# PCB_-_BOARD.net
KiCad netlist of a schematic drawn in EAGLE
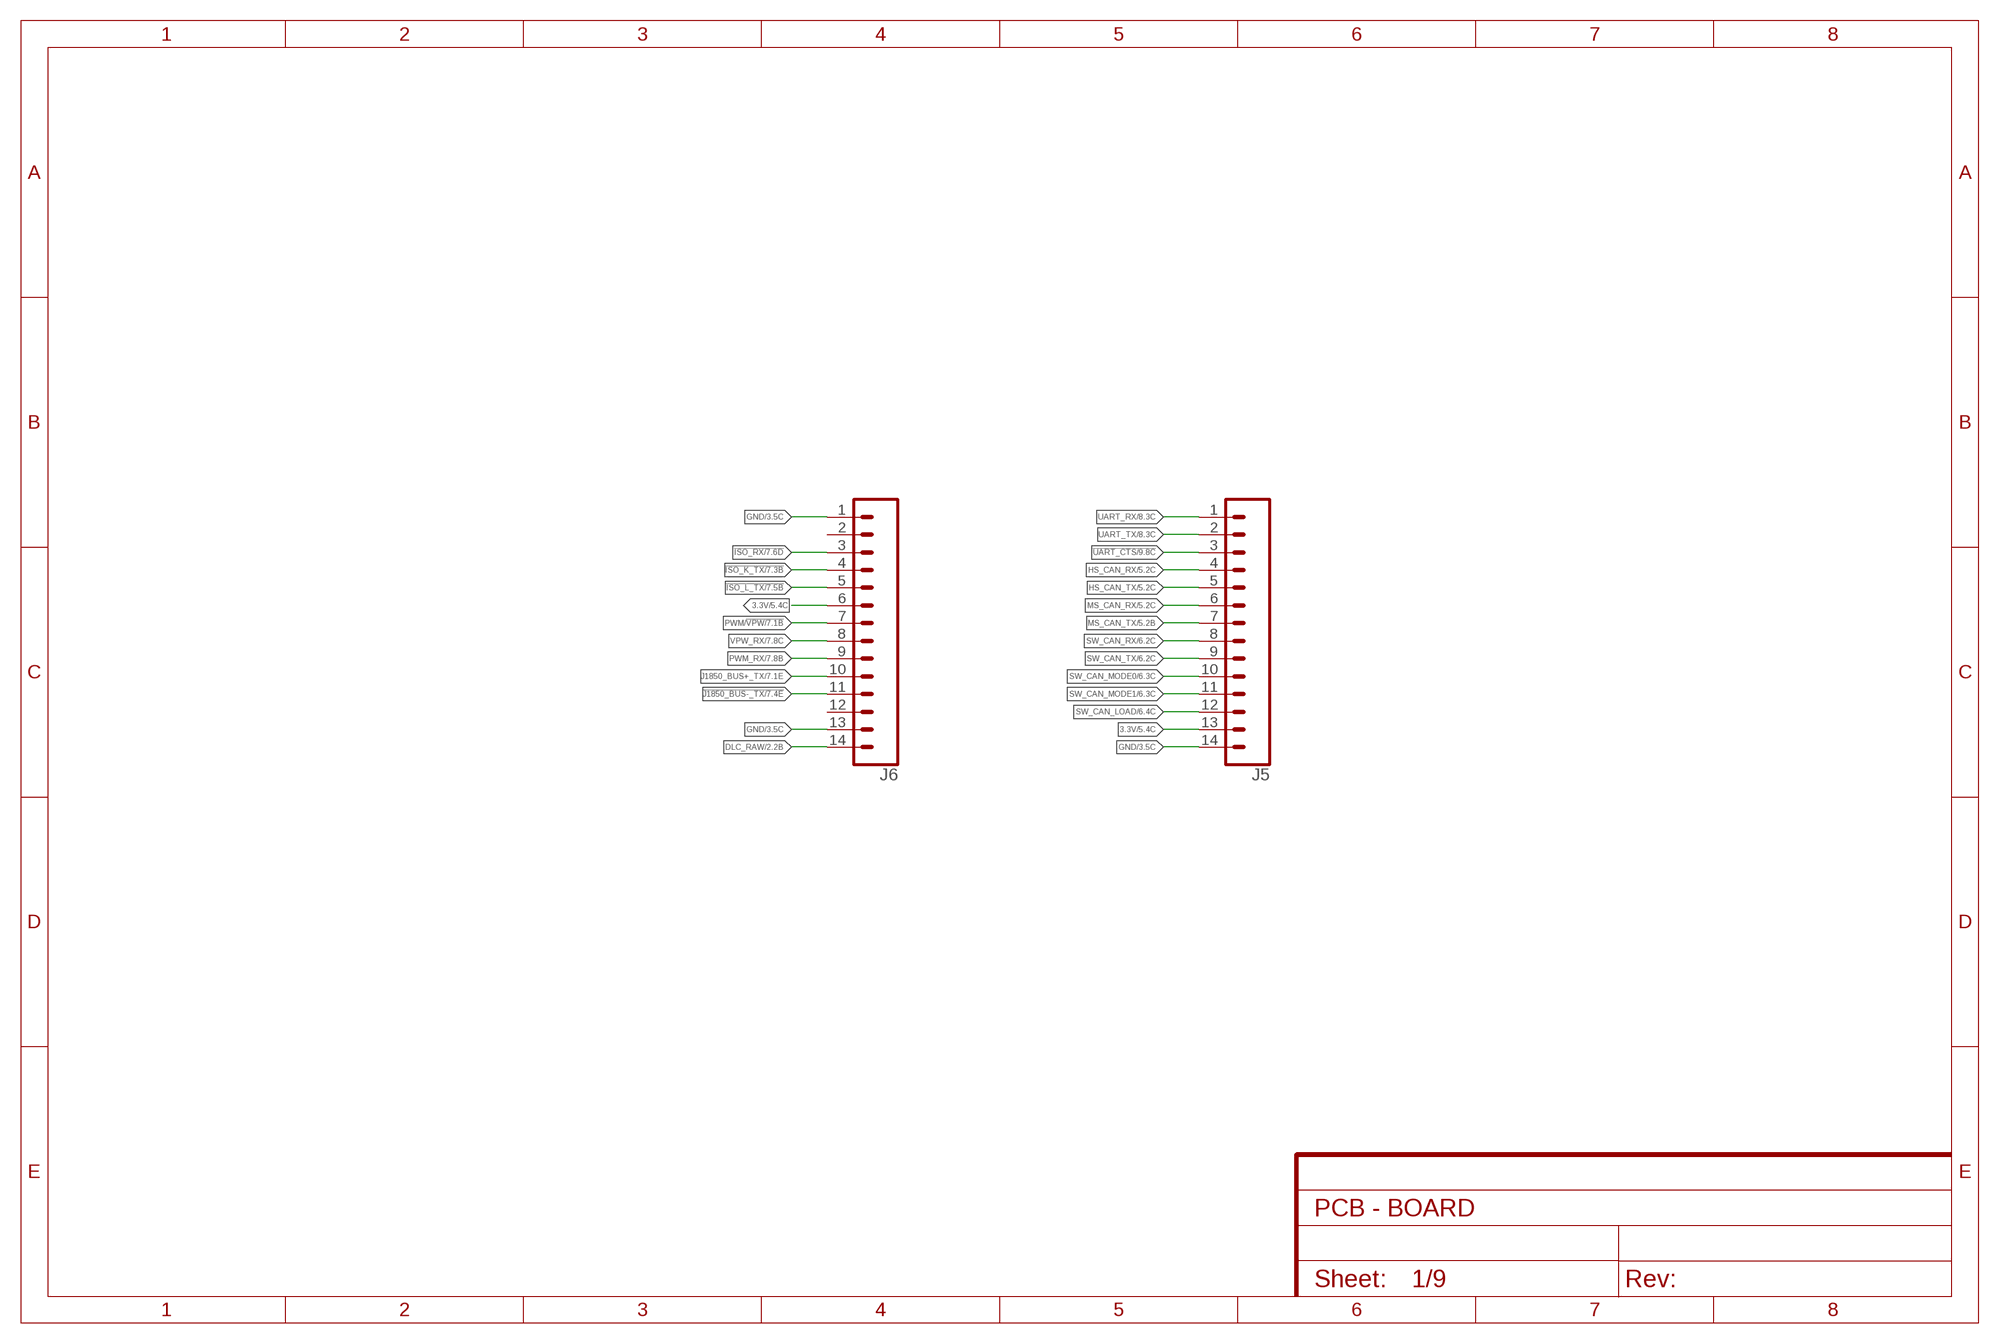
[diagram p0: schematic, sheet 1]
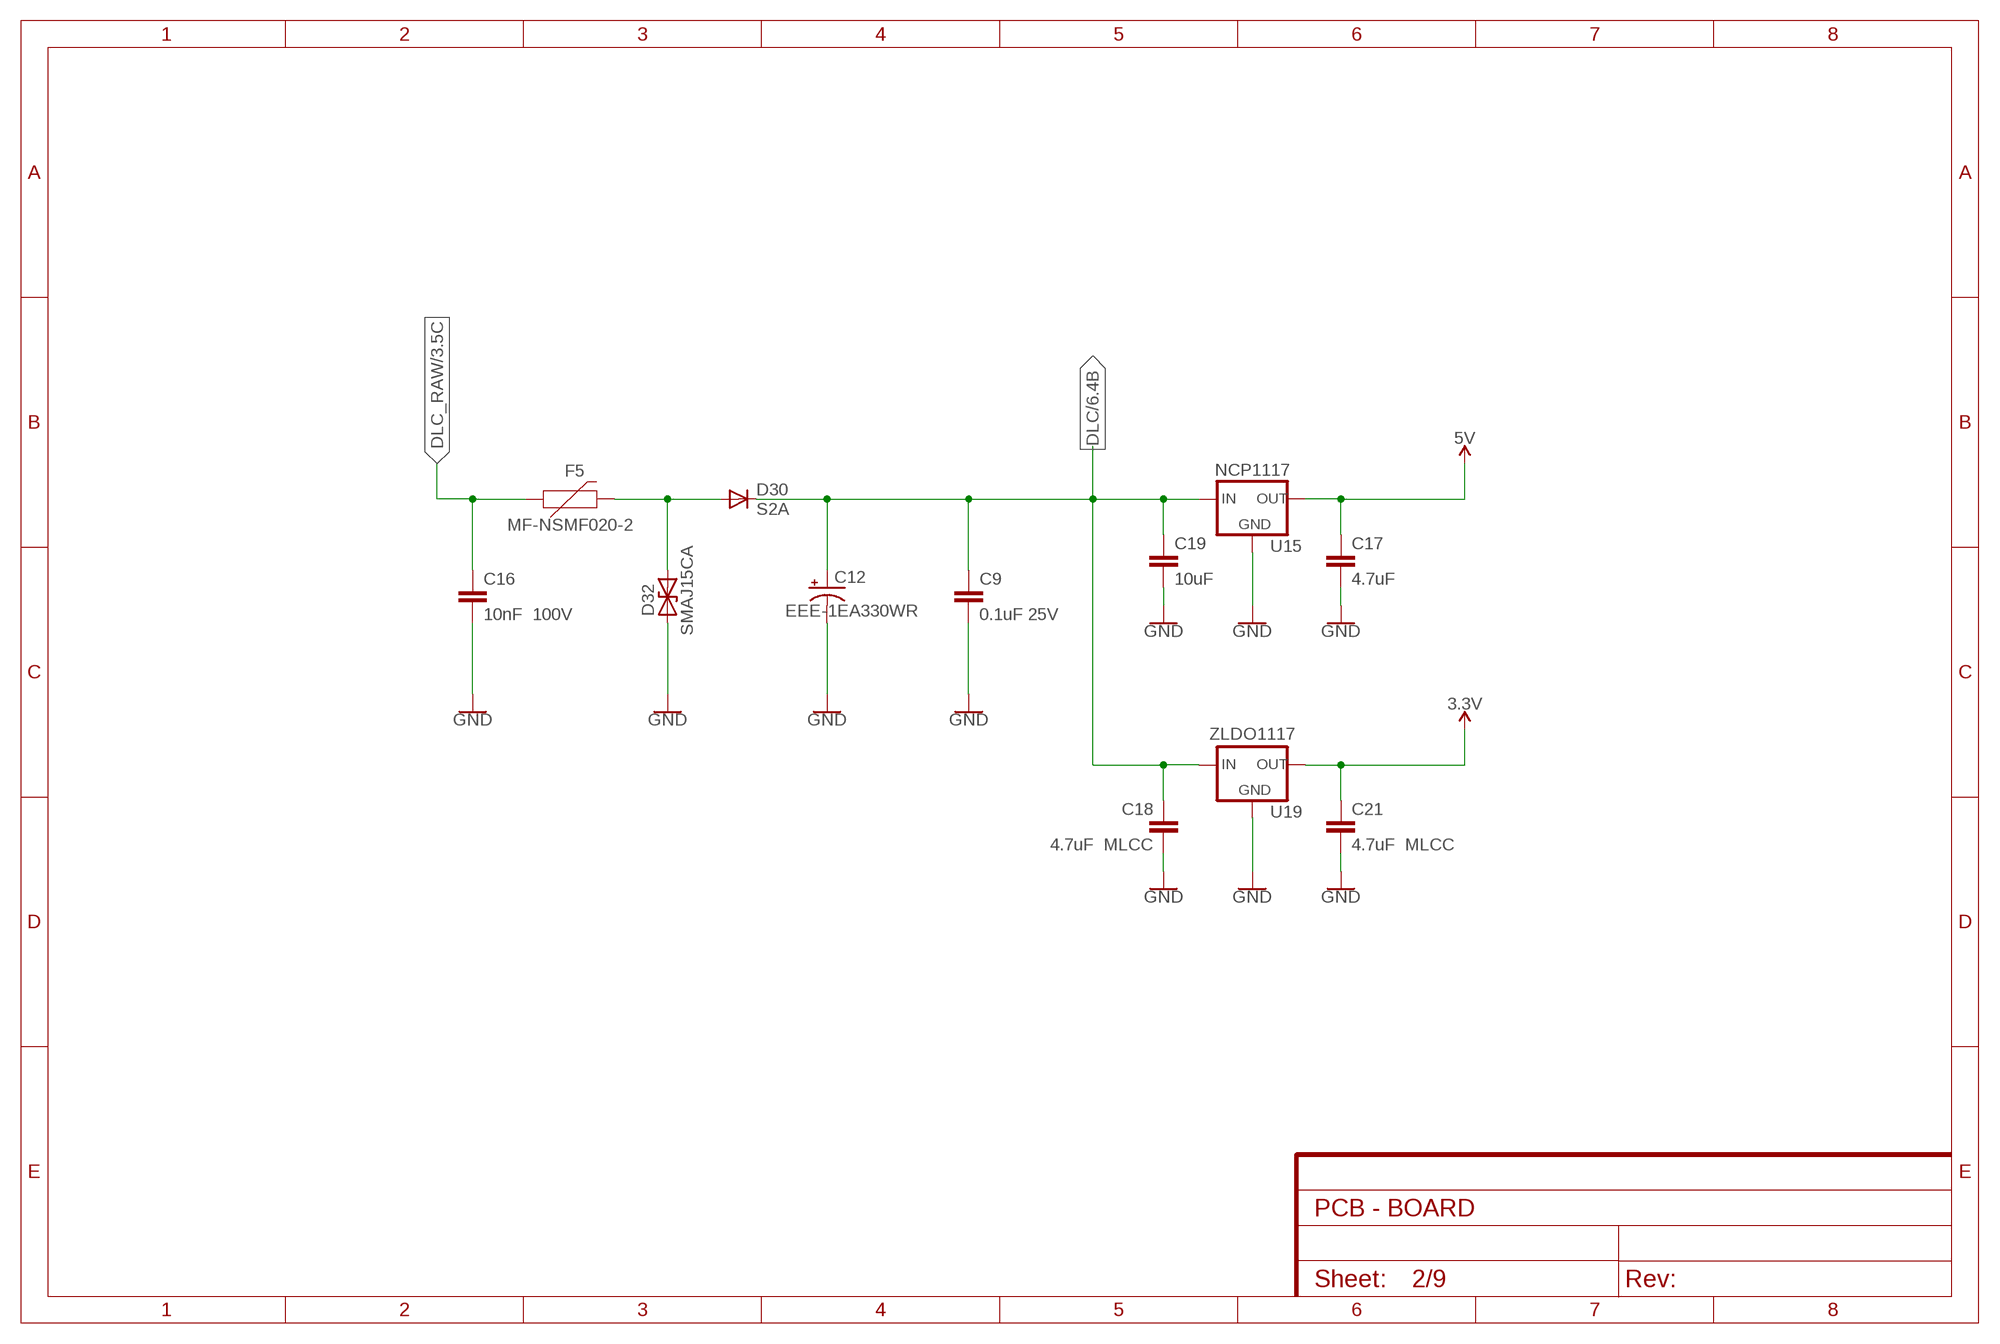
[diagram p1: schematic, sheet 2]
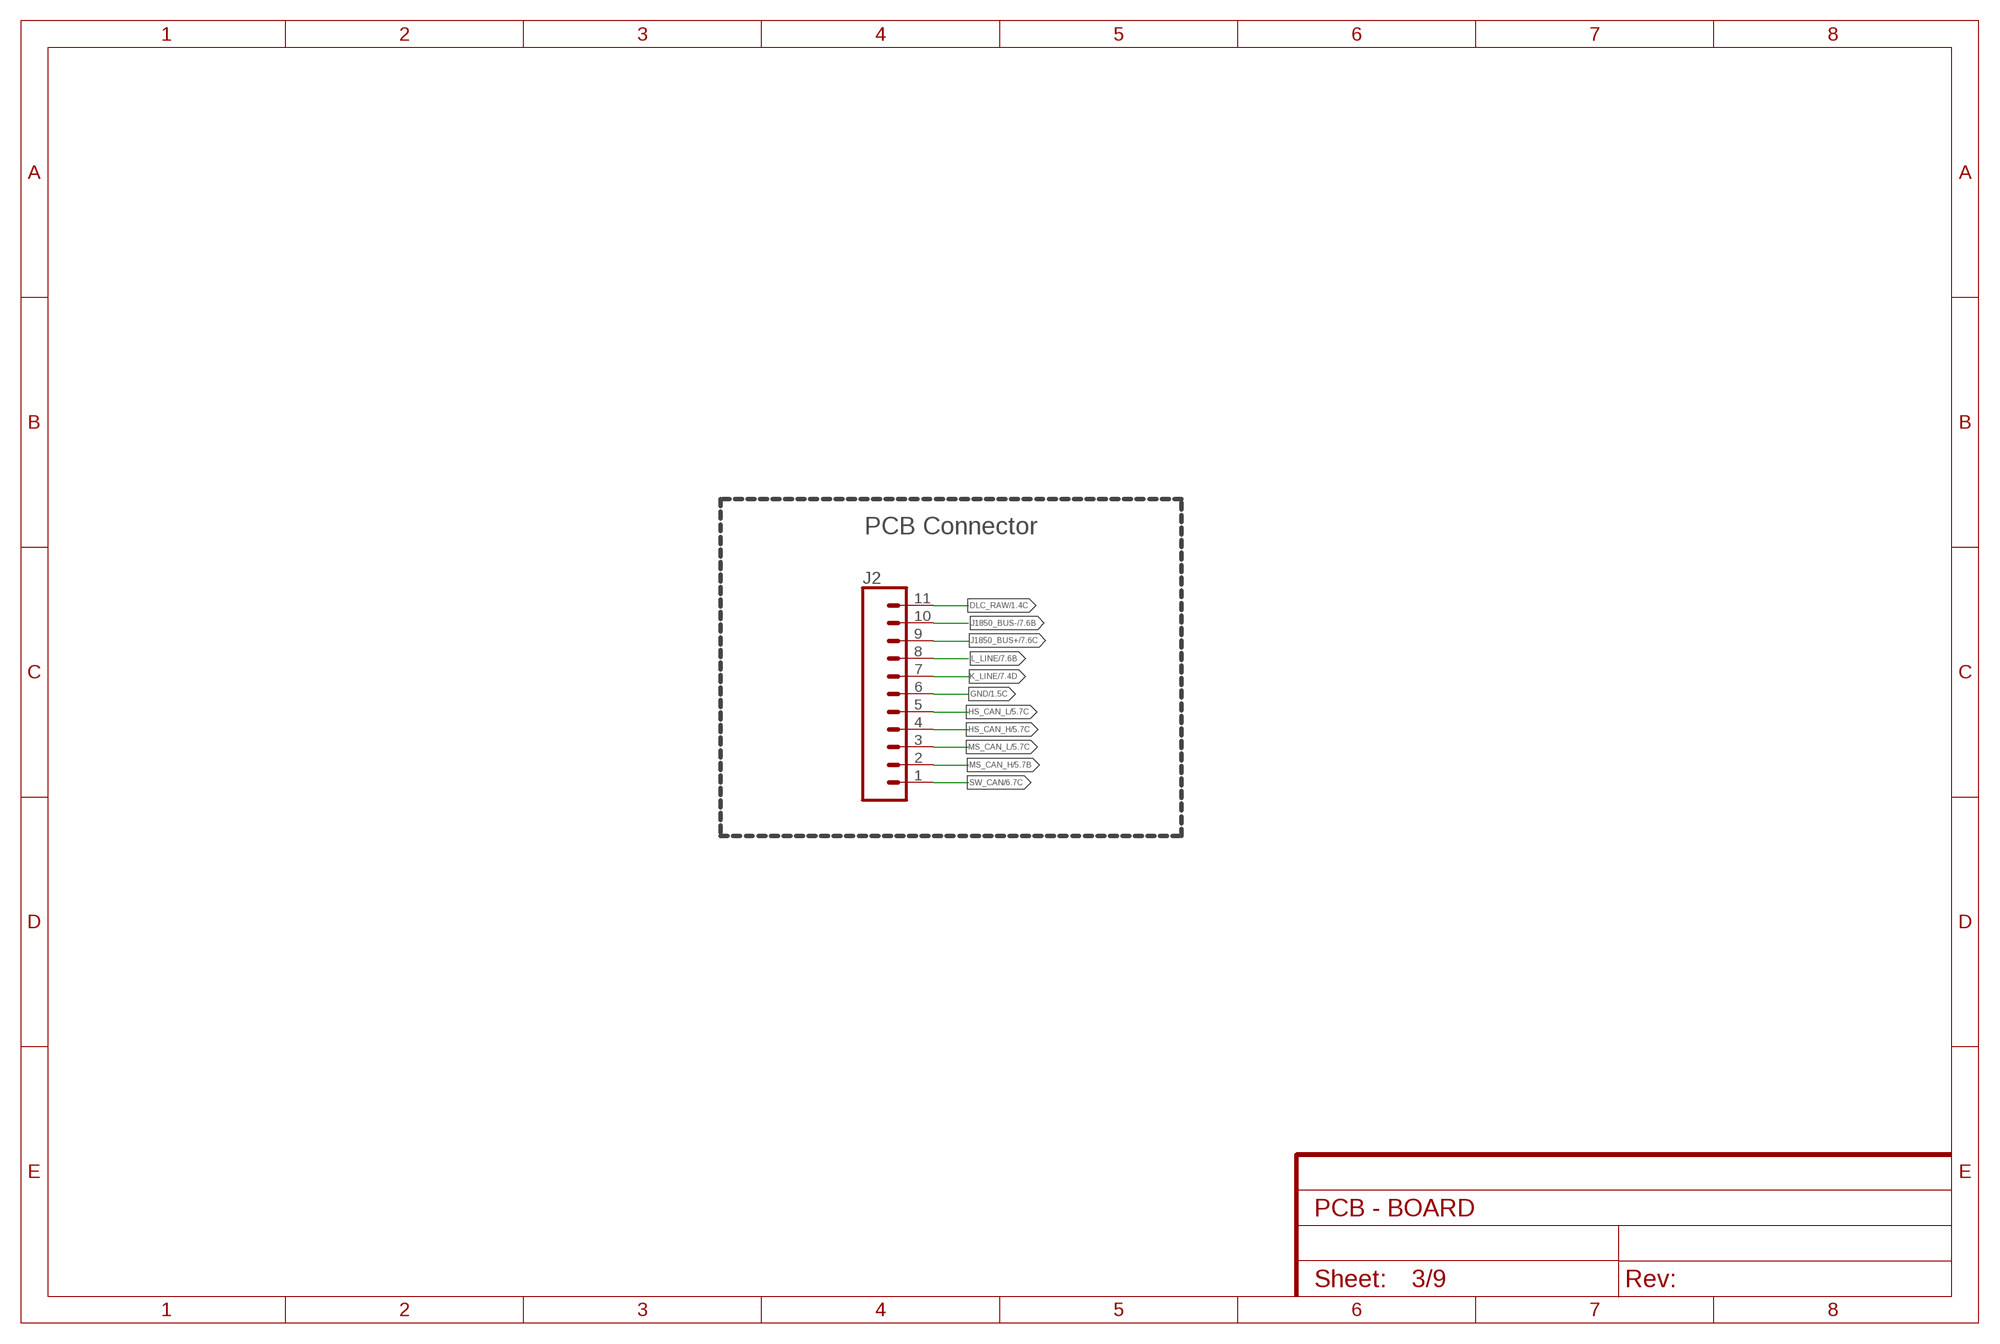
[diagram p2: schematic, sheet 3]
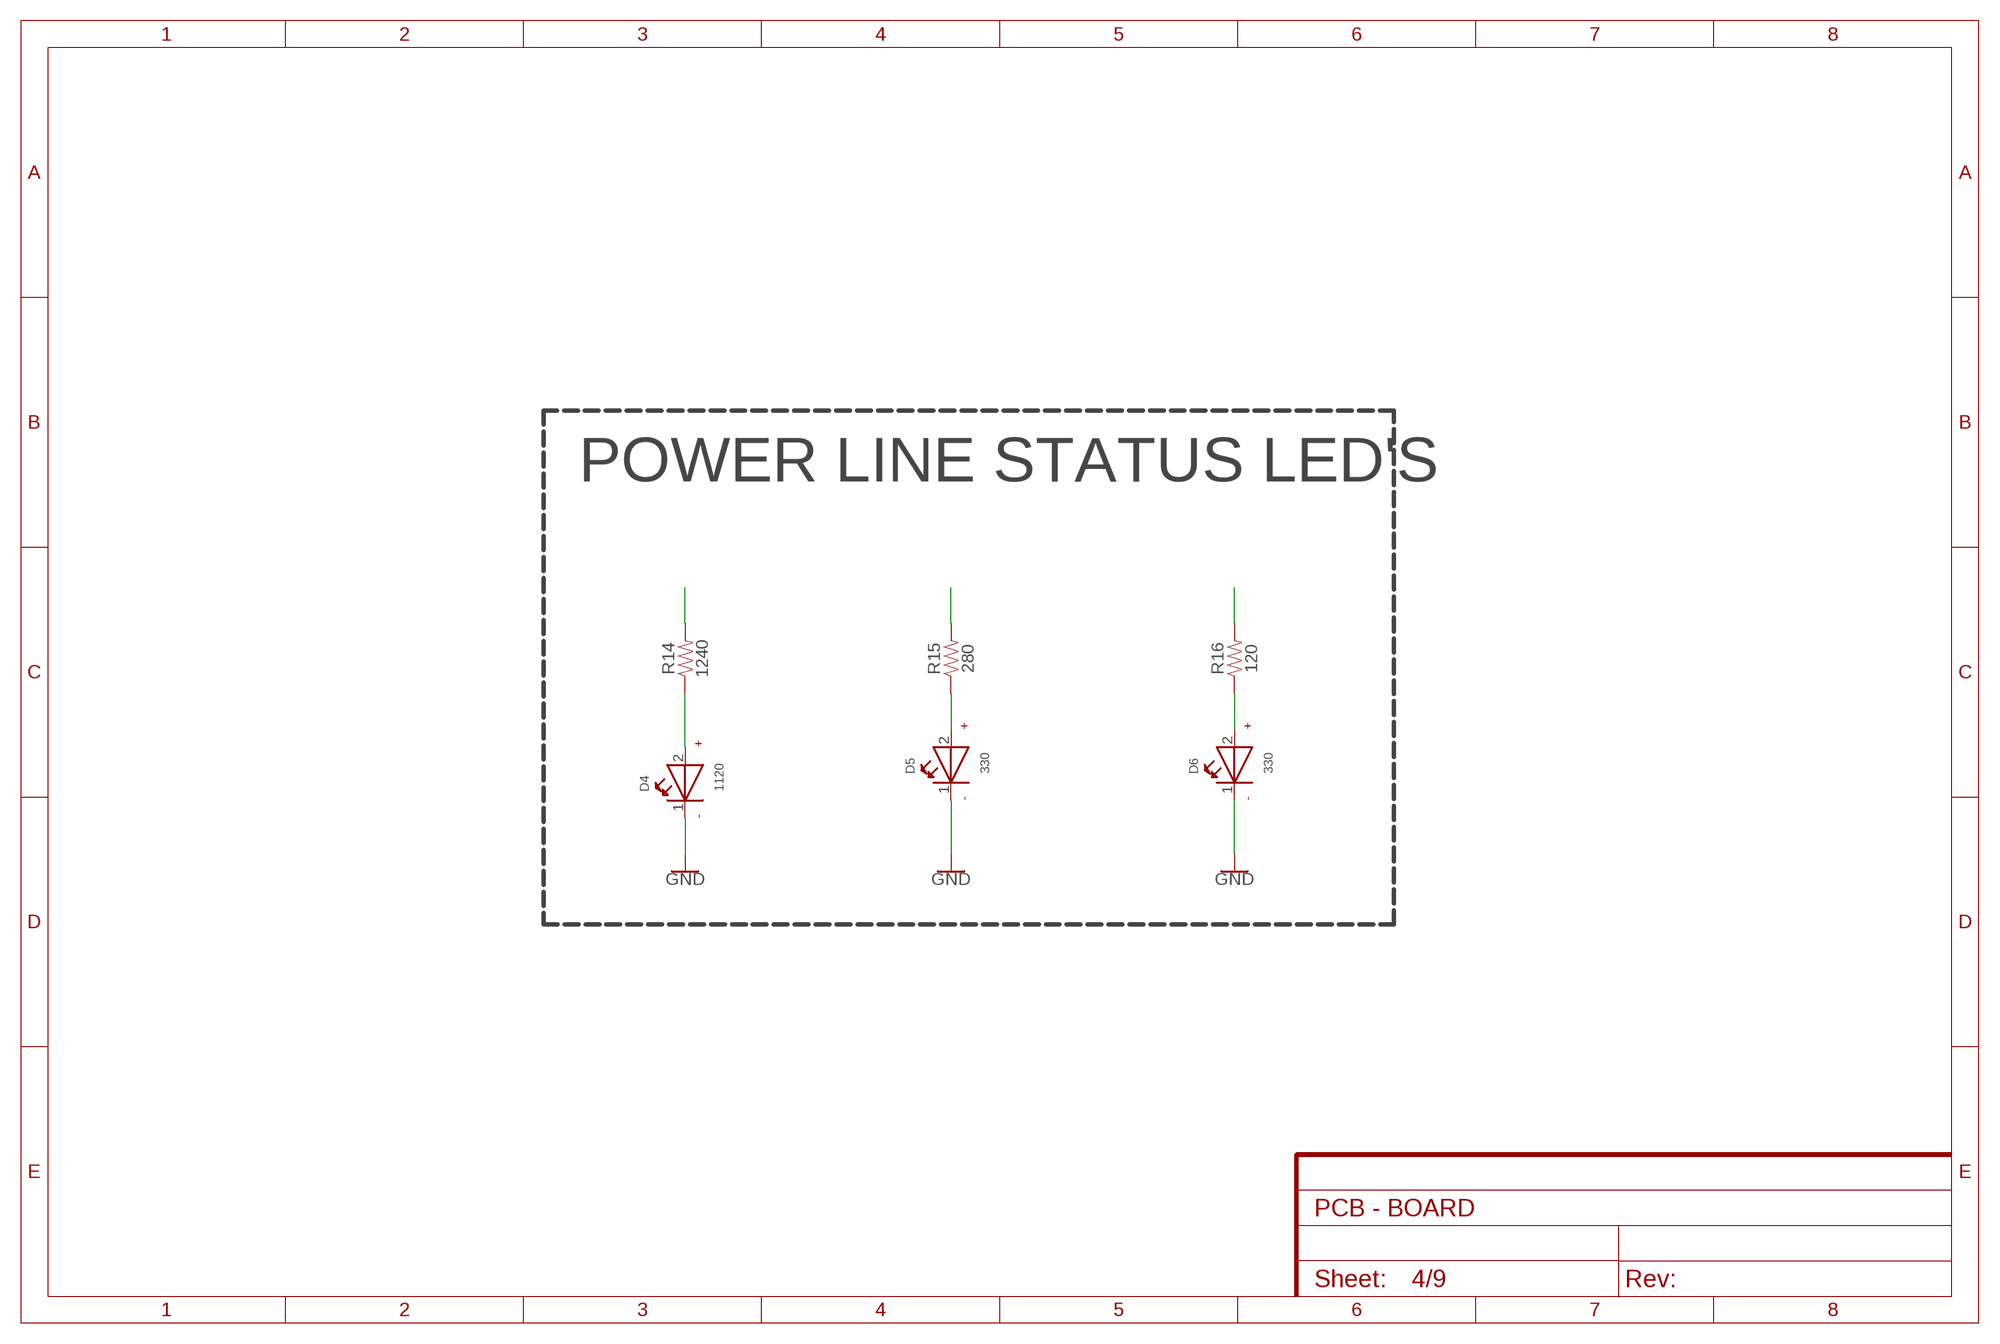
[diagram p3: schematic, sheet 4]
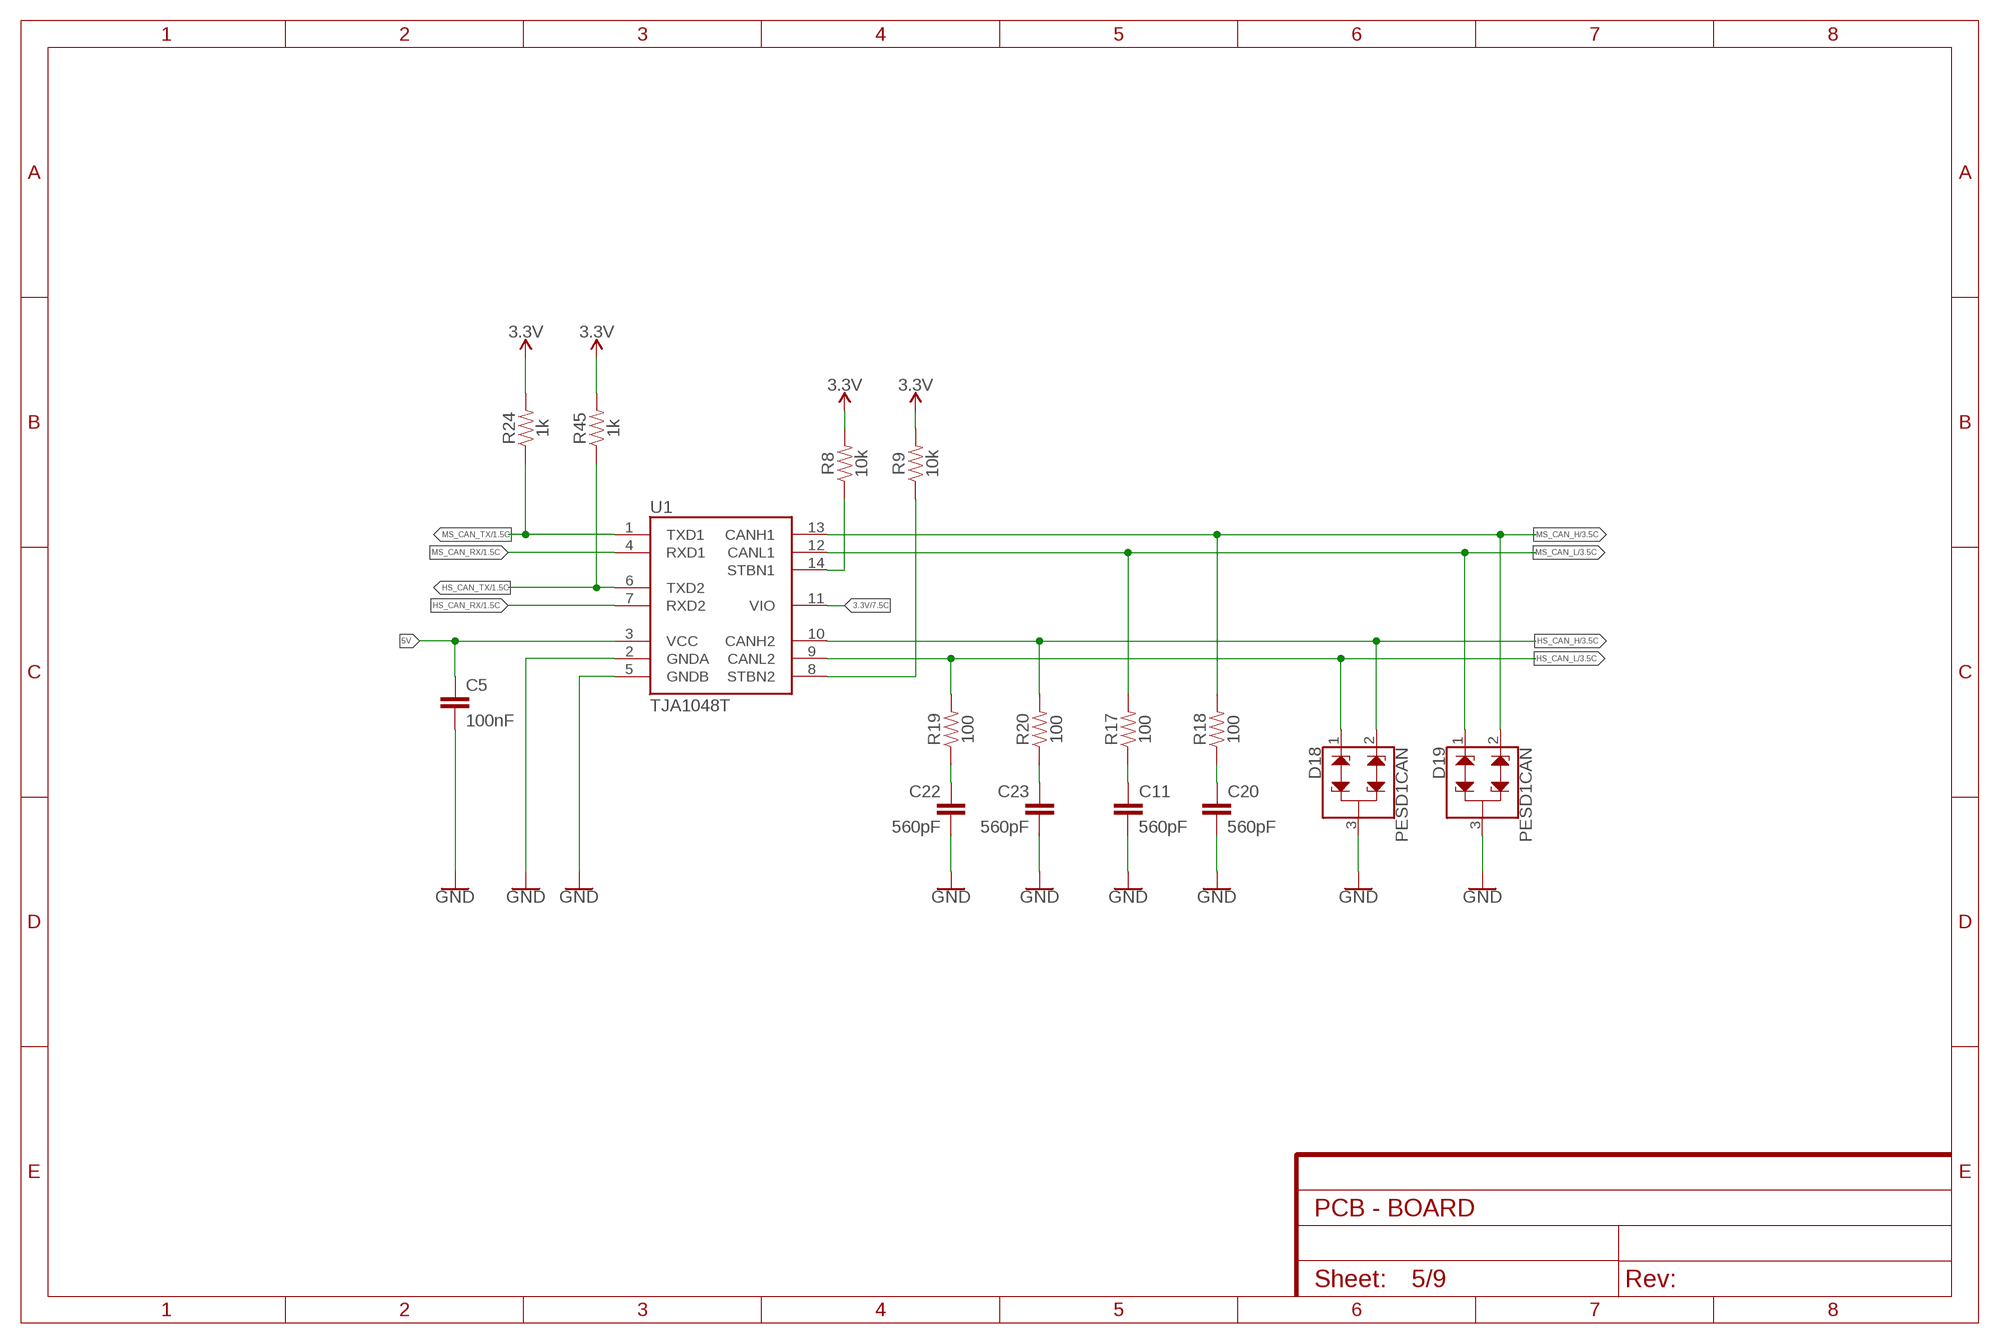
[diagram p4: schematic, sheet 5]
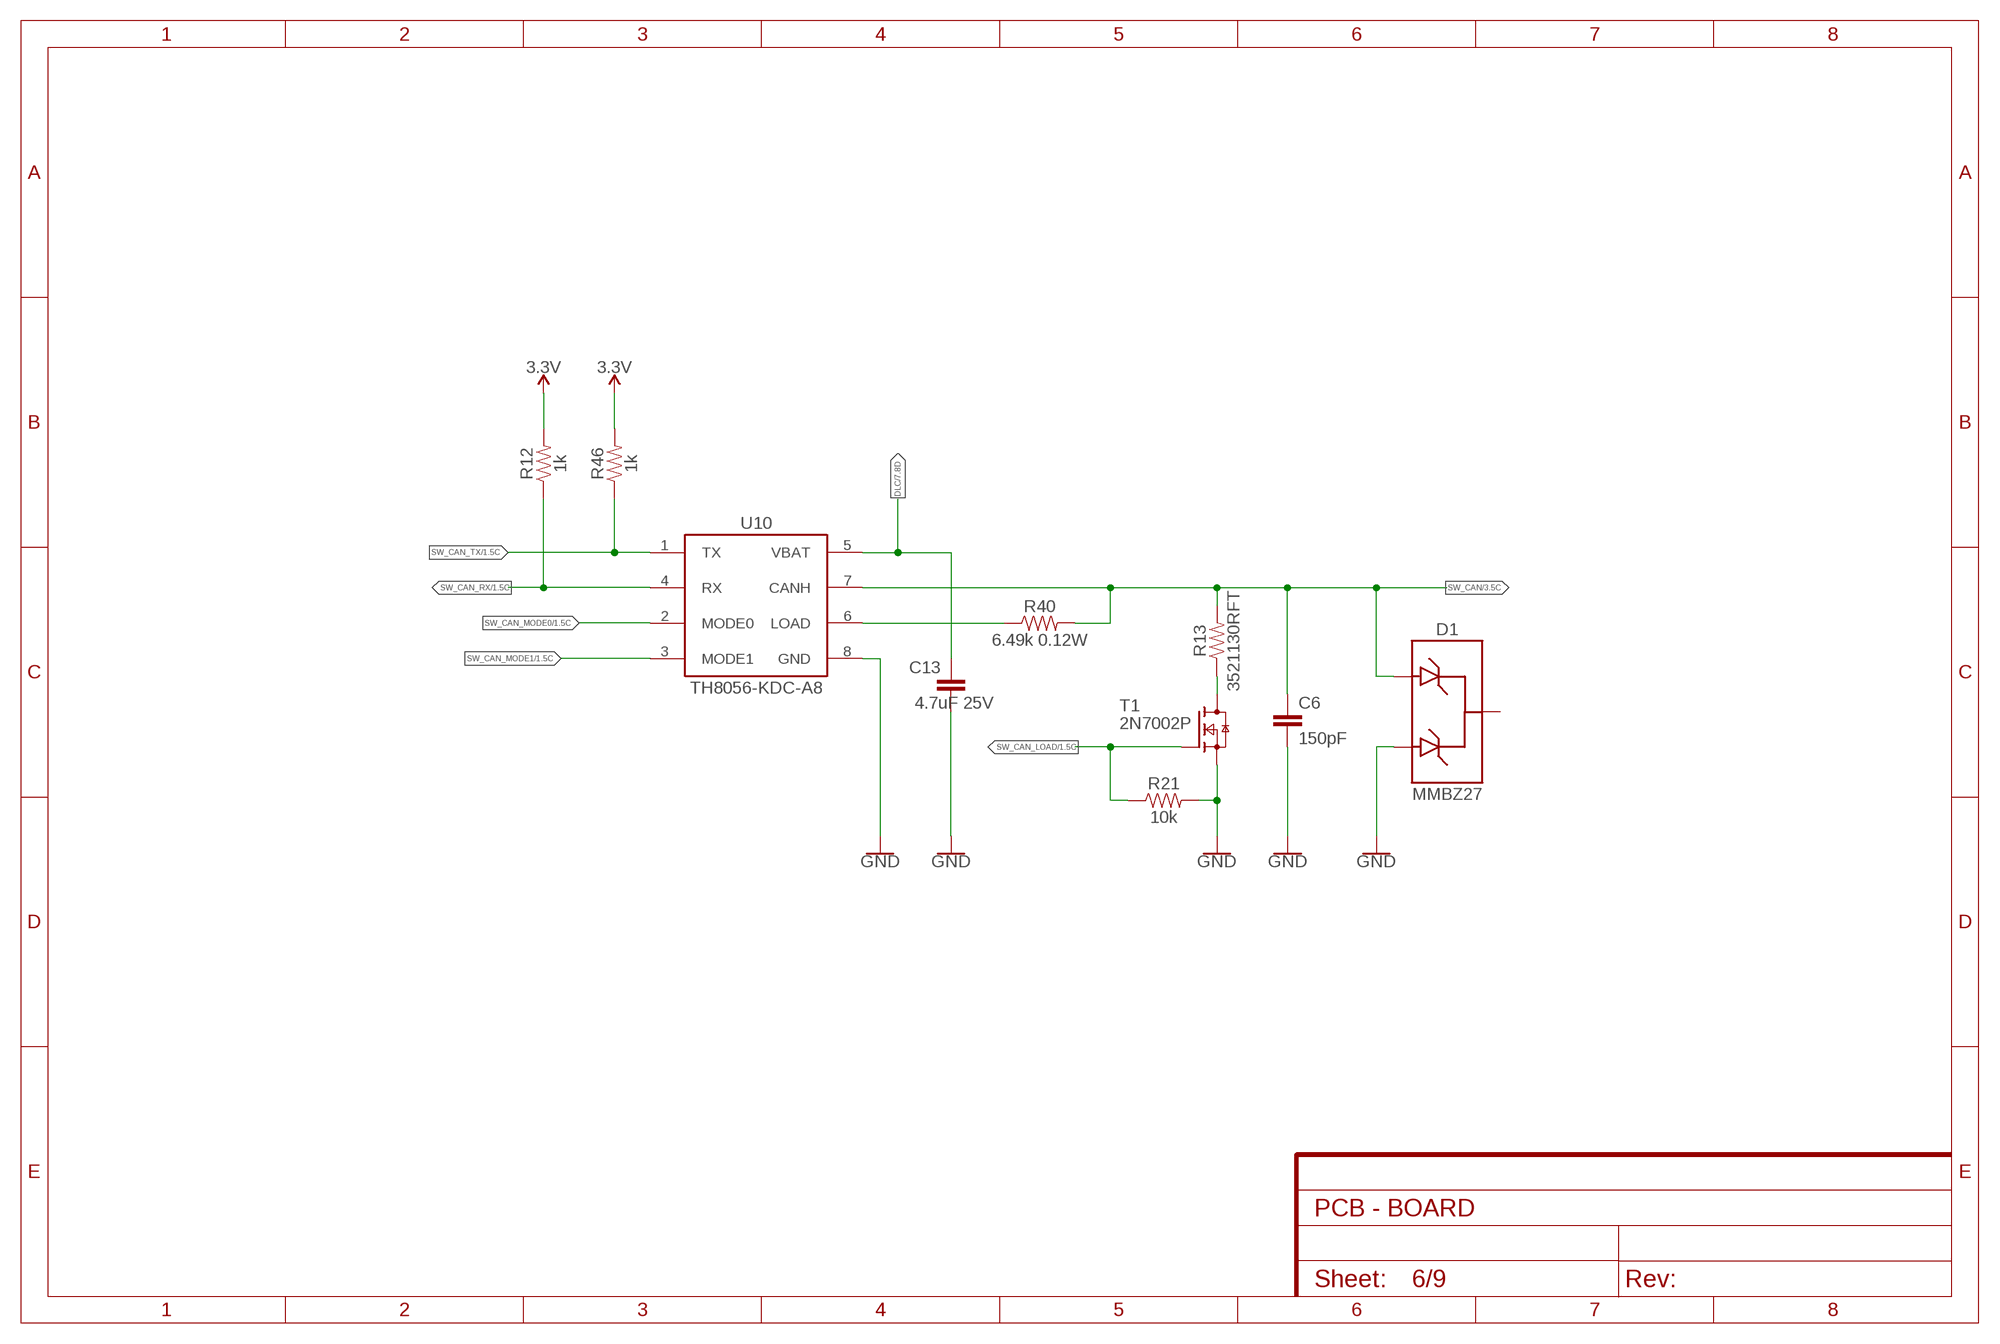
[diagram p5: schematic, sheet 6]
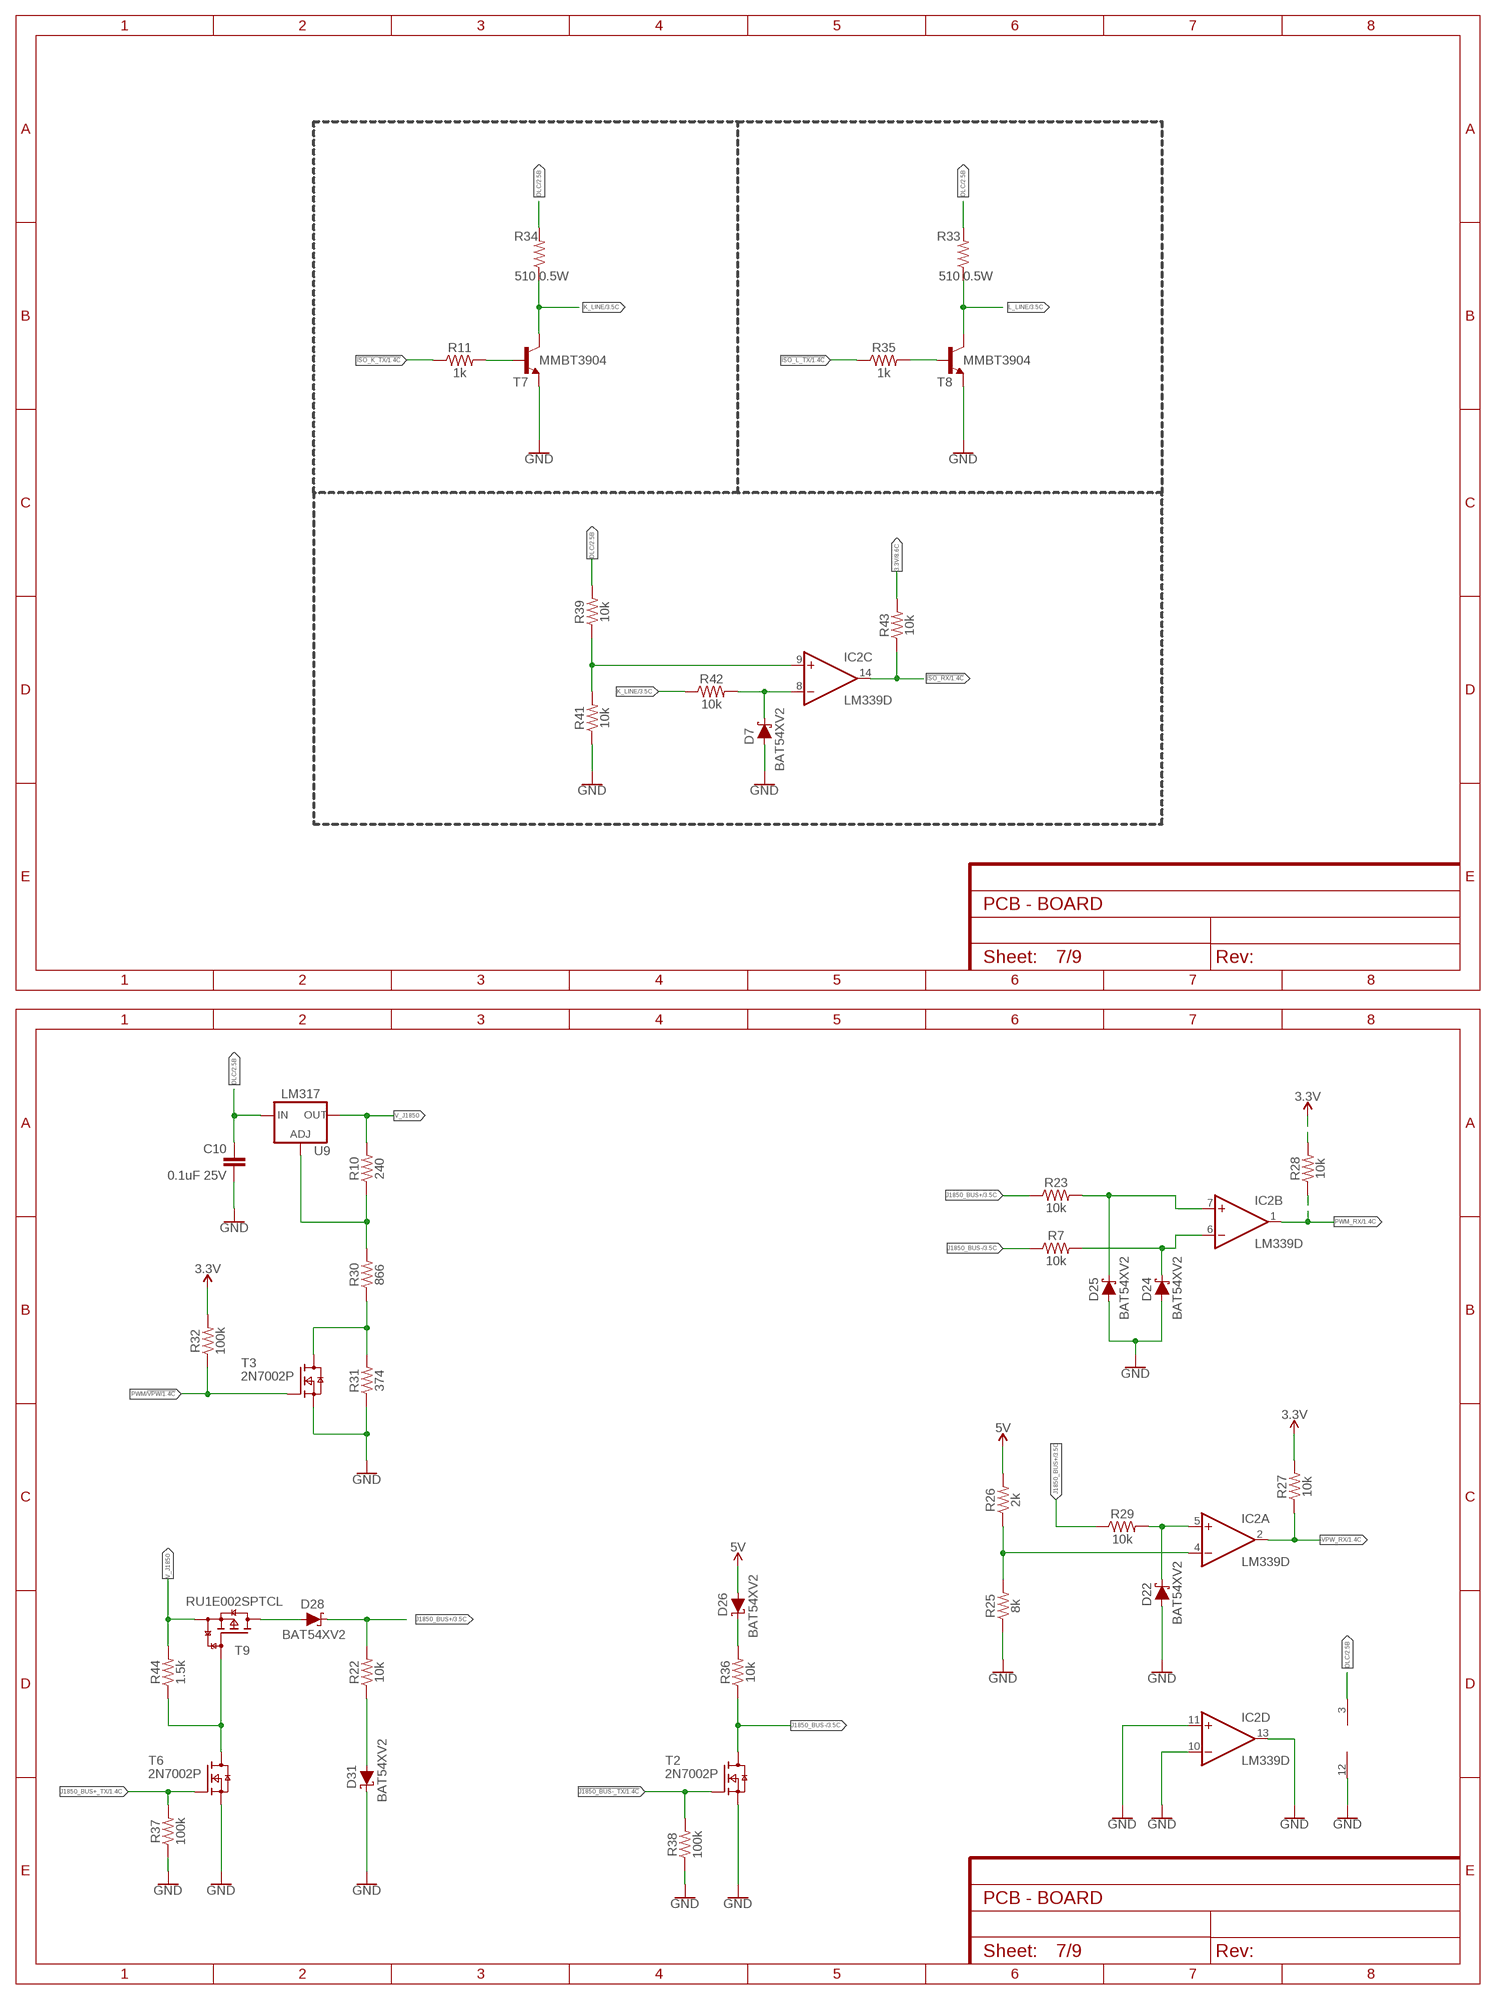
[diagram p6: schematic, sheet 7]
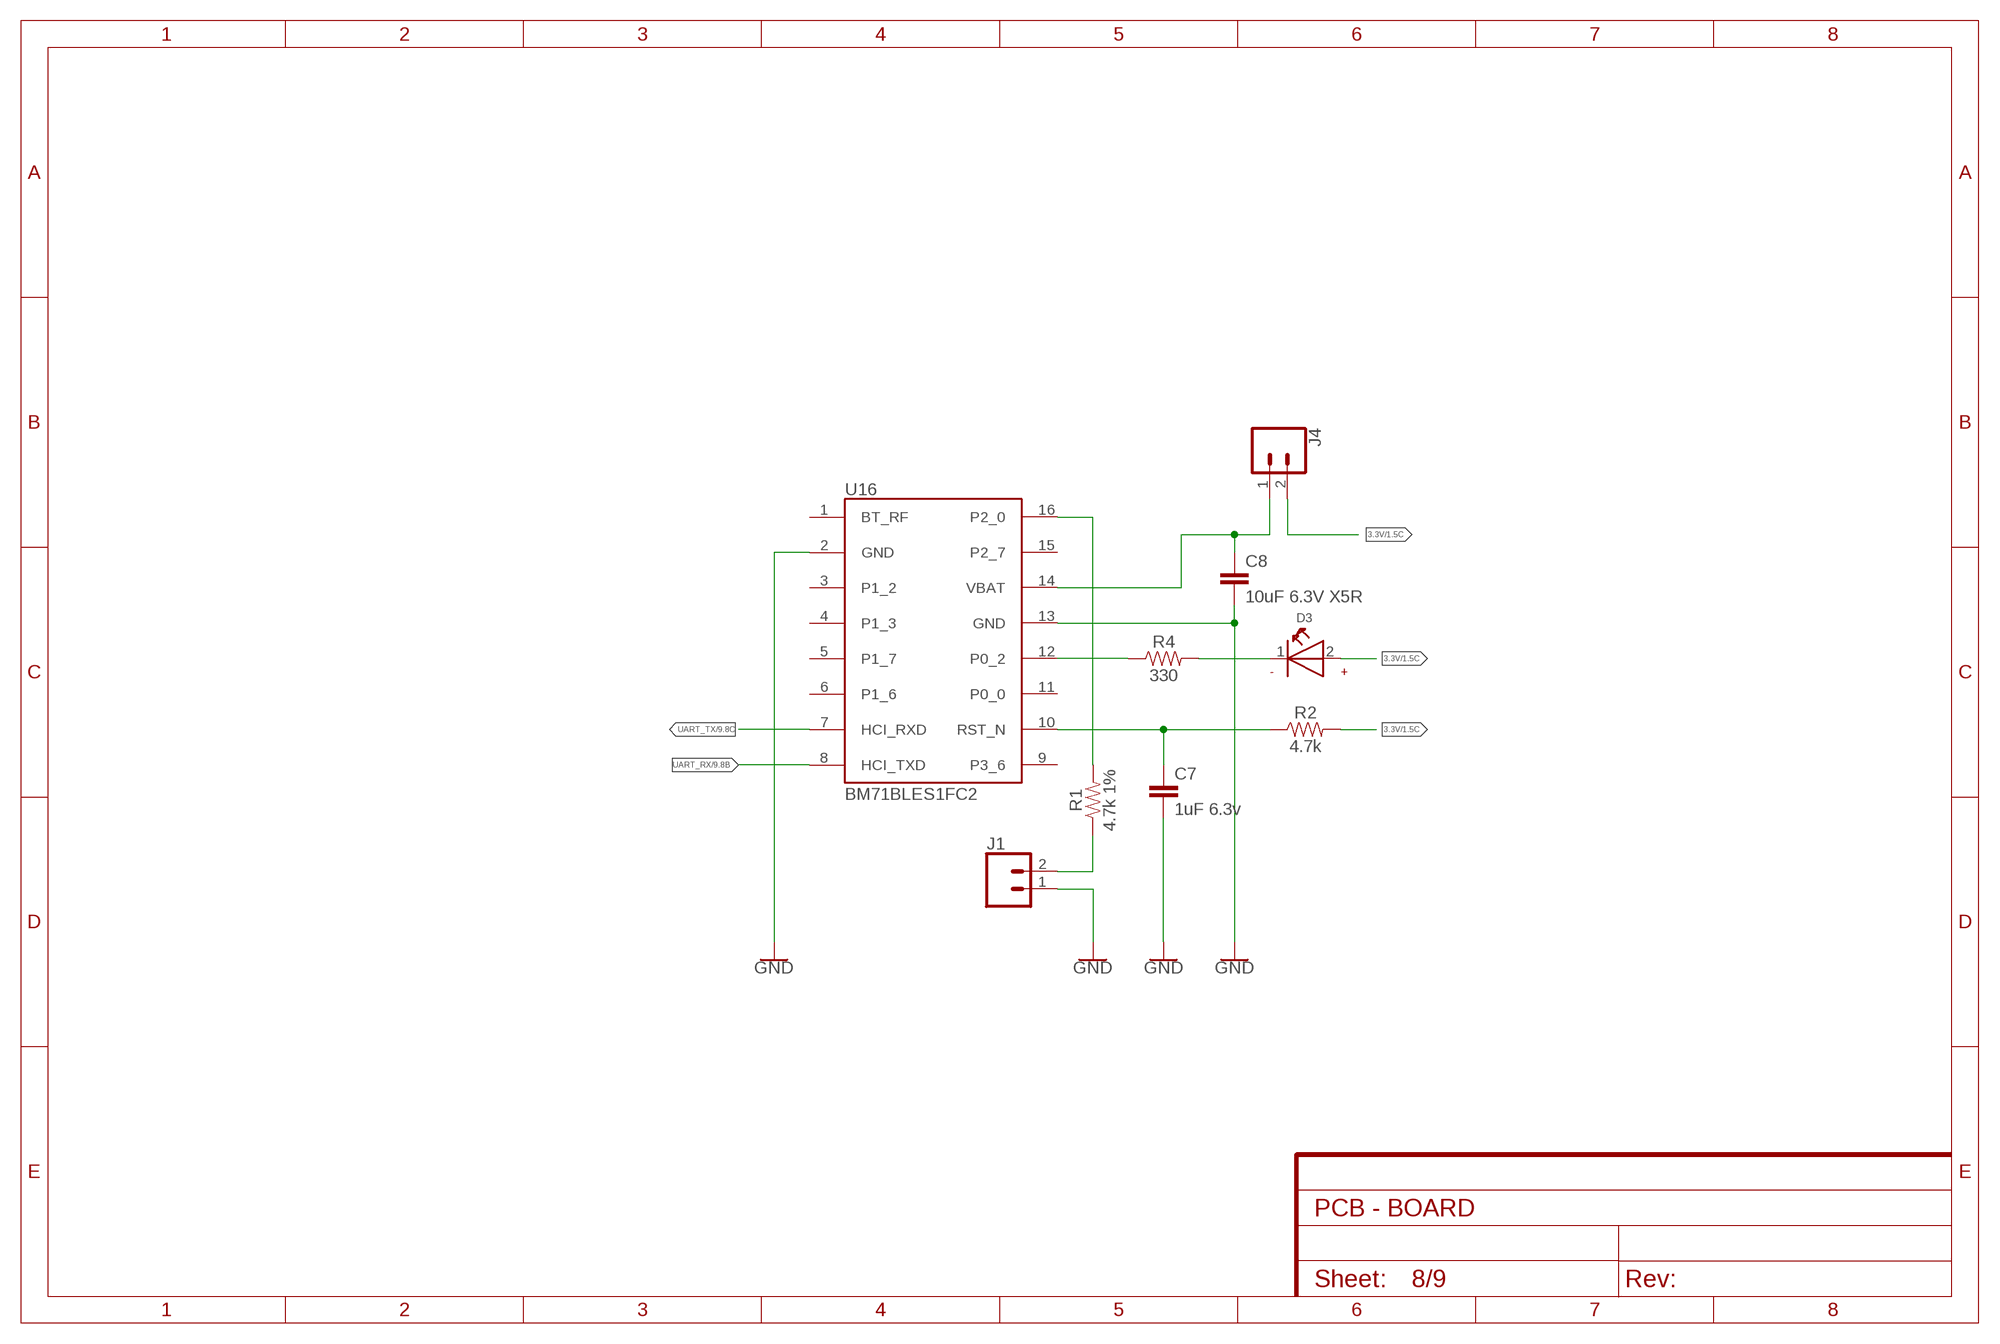
[diagram p7: schematic, sheet 8]
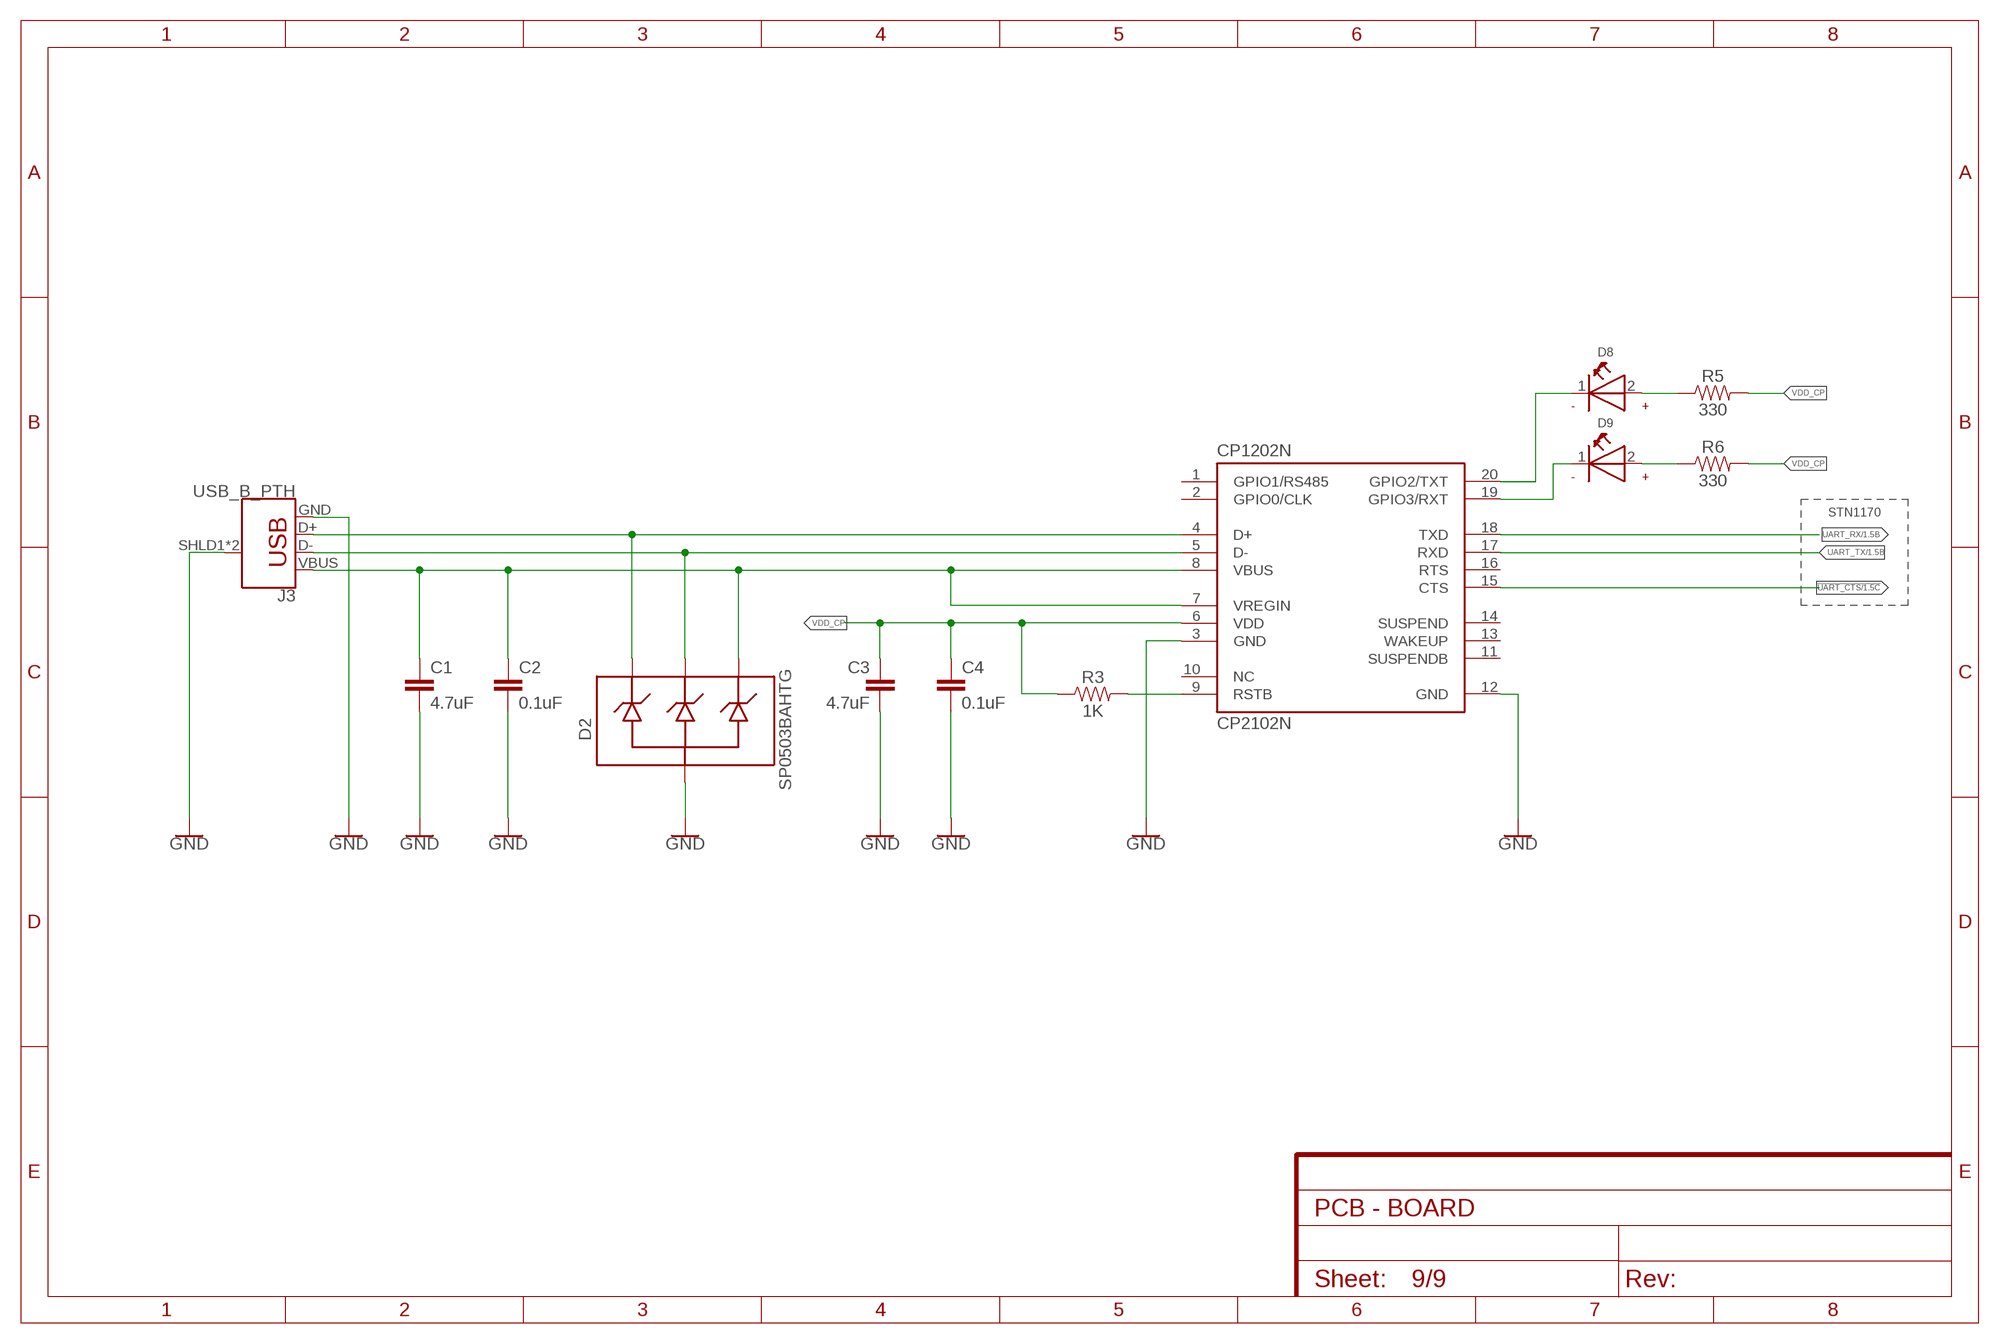
[diagram p8: schematic, sheet 9]

(export (version "E")
  (design (tool "Eeschema 10.0.6"))
  (components
    (comp (ref "J5")
      (value "CONN_14")
      (footprint "eagle-import:1X14")
      (libsource (lib "eagle-import") (part "CONN_14"))
    )
    (comp (ref "J6")
      (value "CONN_14")
      (footprint "eagle-import:1X14")
      (libsource (lib "eagle-import") (part "CONN_14"))
    )
    (comp (ref "C10")
      (value "0.1uF 25V")
      (footprint "eagle-import:0805")
      (libsource (lib "eagle-import") (part "1.0UF-0805-25V-(+80/-20%)"))
    )
    (comp (ref "D7")
      (value "BAT54XV2")
      (footprint "eagle-import:SOD-523F")
      (libsource (lib "eagle-import") (part "BAT54XV2"))
    )
    (comp (ref "D22")
      (value "BAT54XV2")
      (footprint "eagle-import:SOD-523F")
      (libsource (lib "eagle-import") (part "BAT54XV2"))
    )
    (comp (ref "D24")
      (value "BAT54XV2")
      (footprint "eagle-import:SOD-523F")
      (libsource (lib "eagle-import") (part "BAT54XV2"))
    )
    (comp (ref "D25")
      (value "BAT54XV2")
      (footprint "eagle-import:SOD-523F")
      (libsource (lib "eagle-import") (part "BAT54XV2"))
    )
    (comp (ref "D26")
      (value "BAT54XV2")
      (footprint "eagle-import:SOD-523F")
      (libsource (lib "eagle-import") (part "BAT54XV2"))
    )
    (comp (ref "D28")
      (value "BAT54XV2")
      (footprint "eagle-import:SOD-523F")
      (libsource (lib "eagle-import") (part "BAT54XV2"))
    )
    (comp (ref "D31")
      (value "BAT54XV2")
      (footprint "eagle-import:SOD-523F")
      (libsource (lib "eagle-import") (part "BAT54XV2"))
    )
    (comp (ref "IC2")
      (value "LM339D")
      (footprint "eagle-import:SO14")
      (libsource (lib "eagle-import") (part "LM339D"))
    )
    (comp (ref "R7")
      (value "10k")
      (footprint "eagle-import:0805")
      (libsource (lib "eagle-import") (part "0.3OHM-0805-1/8W-1%"))
    )
    (comp (ref "R10")
      (value "240")
      (footprint "eagle-import:0805")
      (libsource (lib "eagle-import") (part "0.3OHM-0805-1/8W-1%"))
    )
    (comp (ref "R11")
      (value "1k")
      (footprint "eagle-import:0805")
      (libsource (lib "eagle-import") (part "0.3OHM-0805-1/8W-1%"))
    )
    (comp (ref "R22")
      (value "10k")
      (footprint "eagle-import:0805")
      (libsource (lib "eagle-import") (part "0.3OHM-0805-1/8W-1%"))
    )
    (comp (ref "R23")
      (value "10k")
      (footprint "eagle-import:0805")
      (libsource (lib "eagle-import") (part "0.3OHM-0805-1/8W-1%"))
    )
    (comp (ref "R25")
      (value "8k")
      (footprint "eagle-import:0805")
      (libsource (lib "eagle-import") (part "0.3OHM-0805-1/8W-1%"))
    )
    (comp (ref "R26")
      (value "2k")
      (footprint "eagle-import:0805")
      (libsource (lib "eagle-import") (part "0.3OHM-0805-1/8W-1%"))
    )
    (comp (ref "R27")
      (value "10k")
      (footprint "eagle-import:0805")
      (libsource (lib "eagle-import") (part "0.3OHM-0805-1/8W-1%"))
    )
    (comp (ref "R28")
      (value "10k")
      (footprint "eagle-import:0805")
      (libsource (lib "eagle-import") (part "0.3OHM-0805-1/8W-1%"))
    )
    (comp (ref "R29")
      (value "10k")
      (footprint "eagle-import:0805")
      (libsource (lib "eagle-import") (part "0.3OHM-0805-1/8W-1%"))
    )
    (comp (ref "R30")
      (value "866")
      (footprint "eagle-import:0805")
      (libsource (lib "eagle-import") (part "0.3OHM-0805-1/8W-1%"))
    )
    (comp (ref "R31")
      (value "374")
      (footprint "eagle-import:0805")
      (libsource (lib "eagle-import") (part "0.3OHM-0805-1/8W-1%"))
    )
    (comp (ref "R32")
      (value "100k")
      (footprint "eagle-import:0805")
      (libsource (lib "eagle-import") (part "0.3OHM-0805-1/8W-1%"))
    )
    (comp (ref "R33")
      (value "510 0.5W")
      (footprint "eagle-import:1210")
      (libsource (lib "eagle-import") (part "0.1OHM-1210-1/2W-1%"))
    )
    (comp (ref "R34")
      (value "510 0.5W")
      (footprint "eagle-import:1210")
      (libsource (lib "eagle-import") (part "0.1OHM-1210-1/2W-1%"))
    )
    (comp (ref "R35")
      (value "1k")
      (footprint "eagle-import:0805")
      (libsource (lib "eagle-import") (part "0.3OHM-0805-1/8W-1%"))
    )
    (comp (ref "R36")
      (value "10k")
      (footprint "eagle-import:0805")
      (libsource (lib "eagle-import") (part "0.3OHM-0805-1/8W-1%"))
    )
    (comp (ref "R37")
      (value "100k")
      (footprint "eagle-import:0805")
      (libsource (lib "eagle-import") (part "0.3OHM-0805-1/8W-1%"))
    )
    (comp (ref "R38")
      (value "100k")
      (footprint "eagle-import:0805")
      (libsource (lib "eagle-import") (part "0.3OHM-0805-1/8W-1%"))
    )
    (comp (ref "R39")
      (value "10k")
      (footprint "eagle-import:0805")
      (libsource (lib "eagle-import") (part "0.3OHM-0805-1/8W-1%"))
    )
    (comp (ref "R41")
      (value "10k")
      (footprint "eagle-import:0805")
      (libsource (lib "eagle-import") (part "0.3OHM-0805-1/8W-1%"))
    )
    (comp (ref "R42")
      (value "10k")
      (footprint "eagle-import:0805")
      (libsource (lib "eagle-import") (part "0.3OHM-0805-1/8W-1%"))
    )
    (comp (ref "R43")
      (value "10k")
      (footprint "eagle-import:0805")
      (libsource (lib "eagle-import") (part "0.3OHM-0805-1/8W-1%"))
    )
    (comp (ref "R44")
      (value "1.5k")
      (footprint "eagle-import:0805")
      (libsource (lib "eagle-import") (part "0.3OHM-0805-1/8W-1%"))
    )
    (comp (ref "T2")
      (value "2N7002P")
      (footprint "eagle-import:SOT23")
      (libsource (lib "eagle-import") (part "2N7002P"))
    )
    (comp (ref "T3")
      (value "2N7002P")
      (footprint "eagle-import:SOT23")
      (libsource (lib "eagle-import") (part "2N7002P"))
    )
    (comp (ref "T6")
      (value "2N7002P")
      (footprint "eagle-import:SOT23")
      (libsource (lib "eagle-import") (part "2N7002P"))
    )
    (comp (ref "T7")
      (value "MMBT3904")
      (footprint "eagle-import:SOT23-BEC")
      (libsource (lib "eagle-import") (part "-NPN-SOT23-BECMMBT3904LT1"))
    )
    (comp (ref "T8")
      (value "MMBT3904")
      (footprint "eagle-import:SOT23-BEC")
      (libsource (lib "eagle-import") (part "-NPN-SOT23-BECMMBT3904LT1"))
    )
    (comp (ref "T9")
      (value "RU1E002SPTCL")
      (footprint "eagle-import:SOT323")
      (libsource (lib "eagle-import") (part "BSS84AKW"))
    )
    (comp (ref "U9")
      (value "LM317")
      (footprint "eagle-import:SOT223")
      (libsource (lib "eagle-import") (part "V_REG_317SMD"))
    )
    (comp (ref "C9")
      (value "0.1uF 25V")
      (footprint "eagle-import:0805")
      (libsource (lib "eagle-import") (part "1.0UF-0805-25V-(+80/-20%)"))
    )
    (comp (ref "C12")
      (value "EEE-1EA330WR")
      (footprint "eagle-import:PANASONIC-C")
      (libsource (lib "eagle-import") (part "EEE-1EA330WR"))
    )
    (comp (ref "C16")
      (value "10nF 100V")
      (footprint "eagle-import:0805")
      (libsource (lib "eagle-import") (part "1.0UF-0805-25V-(+80/-20%)"))
    )
    (comp (ref "C17")
      (value "4.7uF")
      (footprint "eagle-import:0805")
      (libsource (lib "eagle-import") (part "1.0UF-0805-25V-(+80/-20%)"))
    )
    (comp (ref "C18")
      (value "4.7uF MLCC")
      (footprint "eagle-import:0805")
      (libsource (lib "eagle-import") (part "1.0UF-0805-25V-(+80/-20%)"))
    )
    (comp (ref "C19")
      (value "10uF")
      (footprint "eagle-import:0805")
      (libsource (lib "eagle-import") (part "1.0UF-0805-25V-(+80/-20%)"))
    )
    (comp (ref "C21")
      (value "4.7uF MLCC")
      (footprint "eagle-import:0805")
      (libsource (lib "eagle-import") (part "1.0UF-0805-25V-(+80/-20%)"))
    )
    (comp (ref "D30")
      (value "S2A")
      (footprint "eagle-import:DO214AA")
      (fields (field (name "MF") "Fairchild"))
      (libsource (lib "eagle-import") (part "S2A"))
    )
    (comp (ref "D32")
      (value "SMAJ15CA")
      (footprint "eagle-import:DO214AC")
      (fields (field (name "MF") "Littelfuse"))
      (libsource (lib "eagle-import") (part "SMAJCA15"))
    )
    (comp (ref "F5")
      (value "MF-NSMF020-2")
      (footprint "eagle-import:1206")
      (libsource (lib "eagle-import") (part "PPTC_THREE-QUARTER-AMP"))
    )
    (comp (ref "U15")
      (value "NCP1117")
      (footprint "eagle-import:TO-252")
      (libsource (lib "eagle-import") (part "NCP1117DPAK"))
    )
    (comp (ref "U19")
      (value "ZLDO1117")
      (footprint "eagle-import:SOT223")
      (libsource (lib "eagle-import") (part "ZLODO1117SOT223"))
    )
    (comp (ref "C5")
      (value "100nF")
      (footprint "eagle-import:0805")
      (libsource (lib "eagle-import") (part "1.0UF-0805-25V-(+80/-20%)"))
    )
    (comp (ref "C11")
      (value "560pF")
      (footprint "eagle-import:0805")
      (libsource (lib "eagle-import") (part "1.0UF-0805-25V-(+80/-20%)"))
    )
    (comp (ref "C20")
      (value "560pF")
      (footprint "eagle-import:0805")
      (libsource (lib "eagle-import") (part "1.0UF-0805-25V-(+80/-20%)"))
    )
    (comp (ref "C22")
      (value "560pF")
      (footprint "eagle-import:0805")
      (libsource (lib "eagle-import") (part "1.0UF-0805-25V-(+80/-20%)"))
    )
    (comp (ref "C23")
      (value "560pF")
      (footprint "eagle-import:0805")
      (libsource (lib "eagle-import") (part "1.0UF-0805-25V-(+80/-20%)"))
    )
    (comp (ref "D18")
      (value "PESD1CAN")
      (footprint "eagle-import:SOT23-3")
      (libsource (lib "eagle-import") (part "PESD1CAN"))
    )
    (comp (ref "D19")
      (value "PESD1CAN")
      (footprint "eagle-import:SOT23-3")
      (libsource (lib "eagle-import") (part "PESD1CAN"))
    )
    (comp (ref "R8")
      (value "10k")
      (footprint "eagle-import:0805")
      (libsource (lib "eagle-import") (part "0.3OHM-0805-1/8W-1%"))
    )
    (comp (ref "R9")
      (value "10k")
      (footprint "eagle-import:0805")
      (libsource (lib "eagle-import") (part "0.3OHM-0805-1/8W-1%"))
    )
    (comp (ref "R17")
      (value "100")
      (footprint "eagle-import:0805")
      (libsource (lib "eagle-import") (part "0.3OHM-0805-1/8W-1%"))
    )
    (comp (ref "R18")
      (value "100")
      (footprint "eagle-import:0805")
      (libsource (lib "eagle-import") (part "0.3OHM-0805-1/8W-1%"))
    )
    (comp (ref "R19")
      (value "100")
      (footprint "eagle-import:0805")
      (libsource (lib "eagle-import") (part "0.3OHM-0805-1/8W-1%"))
    )
    (comp (ref "R20")
      (value "100")
      (footprint "eagle-import:0805")
      (libsource (lib "eagle-import") (part "0.3OHM-0805-1/8W-1%"))
    )
    (comp (ref "R24")
      (value "1k")
      (footprint "eagle-import:0805")
      (libsource (lib "eagle-import") (part "0.3OHM-0805-1/8W-1%"))
    )
    (comp (ref "R45")
      (value "1k")
      (footprint "eagle-import:0805")
      (libsource (lib "eagle-import") (part "0.3OHM-0805-1/8W-1%"))
    )
    (comp (ref "U1")
      (value "TJA1048T")
      (footprint "eagle-import:SO14")
      (libsource (lib "eagle-import") (part "TJA1048T"))
    )
    (comp (ref "D4")
      (value "1120")
      (footprint "eagle-import:WL-SMCW_1206")
      (libsource (lib "eagle-import") (part "WL-SMCW-150120BS75000-B"))
    )
    (comp (ref "D5")
      (value "330")
      (footprint "eagle-import:WL-SMCW_1206")
      (libsource (lib "eagle-import") (part "WL-SMCW-150120BS75000-B"))
    )
    (comp (ref "D6")
      (value "330")
      (footprint "eagle-import:WL-SMCW_1206")
      (libsource (lib "eagle-import") (part "WL-SMCW-150120BS75000-B"))
    )
    (comp (ref "R14")
      (value "1240")
      (footprint "eagle-import:0805")
      (libsource (lib "eagle-import") (part "0.3OHM-0805-1/8W-1%"))
    )
    (comp (ref "R15")
      (value "280")
      (footprint "eagle-import:0805")
      (libsource (lib "eagle-import") (part "0.3OHM-0805-1/8W-1%"))
    )
    (comp (ref "R16")
      (value "120")
      (footprint "eagle-import:0805")
      (libsource (lib "eagle-import") (part "0.3OHM-0805-1/8W-1%"))
    )
    (comp (ref "C1")
      (value "4.7uF")
      (footprint "eagle-import:0805")
      (libsource (lib "eagle-import") (part "1.0UF-0805-25V-(+80/-20%)"))
    )
    (comp (ref "C2")
      (value "0.1uF")
      (footprint "eagle-import:0805")
      (libsource (lib "eagle-import") (part "1.0UF-0805-25V-(+80/-20%)"))
    )
    (comp (ref "C3")
      (value "4.7uF")
      (footprint "eagle-import:0805")
      (libsource (lib "eagle-import") (part "1.0UF-0805-25V-(+80/-20%)"))
    )
    (comp (ref "C4")
      (value "0.1uF")
      (footprint "eagle-import:0805")
      (libsource (lib "eagle-import") (part "1.0UF-0805-25V-(+80/-20%)"))
    )
    (comp (ref "CP1202N")
      (value "CP2102N")
      (footprint "eagle-import:QFN20")
      (libsource (lib "eagle-import") (part "CP2102N"))
    )
    (comp (ref "D2")
      (value "SP0503BAHTG")
      (footprint "eagle-import:SOT143-4")
      (libsource (lib "eagle-import") (part "SP0503BAHTG"))
    )
    (comp (ref "D8")
      (value "WL-SMCW-150120BS75000-B")
      (footprint "eagle-import:WL-SMCW_1206")
      (libsource (lib "eagle-import") (part "WL-SMCW-150120BS75000-B"))
    )
    (comp (ref "D9")
      (value "WL-SMCW-150120BS75000-B")
      (footprint "eagle-import:WL-SMCW_1206")
      (libsource (lib "eagle-import") (part "WL-SMCW-150120BS75000-B"))
    )
    (comp (ref "J3")
      (value "USB_B_PTH")
      (footprint "eagle-import:USB-B-PTH")
      (libsource (lib "eagle-import") (part "USB_B_PTH"))
    )
    (comp (ref "R3")
      (value "1K")
      (footprint "eagle-import:0805")
      (libsource (lib "eagle-import") (part "0.3OHM-0805-1/8W-1%"))
    )
    (comp (ref "R5")
      (value "330")
      (footprint "eagle-import:0805")
      (libsource (lib "eagle-import") (part "0.3OHM-0805-1/8W-1%"))
    )
    (comp (ref "R6")
      (value "330")
      (footprint "eagle-import:0805")
      (libsource (lib "eagle-import") (part "0.3OHM-0805-1/8W-1%"))
    )
    (comp (ref "C6")
      (value "150pF")
      (footprint "eagle-import:0805")
      (libsource (lib "eagle-import") (part "1.0UF-0805-25V-(+80/-20%)"))
    )
    (comp (ref "C13")
      (value "4.7uF 25V")
      (footprint "eagle-import:0805")
      (libsource (lib "eagle-import") (part "1.0UF-0805-25V-(+80/-20%)"))
    )
    (comp (ref "D1")
      (value "MMBZ27")
      (footprint "eagle-import:SOT23-3")
      (libsource (lib "eagle-import") (part "MMBZ27"))
    )
    (comp (ref "R12")
      (value "1k")
      (footprint "eagle-import:0805")
      (libsource (lib "eagle-import") (part "0.3OHM-0805-1/8W-1%"))
    )
    (comp (ref "R13")
      (value "3521130RFT")
      (footprint "eagle-import:3521")
      (libsource (lib "eagle-import") (part "3521130RFT"))
    )
    (comp (ref "R21")
      (value "10k")
      (footprint "eagle-import:0805")
      (libsource (lib "eagle-import") (part "0.3OHM-0805-1/8W-1%"))
    )
    (comp (ref "R40")
      (value "6.49k 0.12W")
      (footprint "eagle-import:1206")
      (libsource (lib "eagle-import") (part "10OHM-1206-1/4W-1%"))
    )
    (comp (ref "R46")
      (value "1k")
      (footprint "eagle-import:0805")
      (libsource (lib "eagle-import") (part "0.3OHM-0805-1/8W-1%"))
    )
    (comp (ref "T1")
      (value "2N7002P")
      (footprint "eagle-import:SOT23")
      (libsource (lib "eagle-import") (part "2N7002P"))
    )
    (comp (ref "U10")
      (value "TH8056-KDC-A8")
      (footprint "eagle-import:SOIC-8")
      (libsource (lib "eagle-import") (part "TH8056-KDC-A8"))
    )
    (comp (ref "C7")
      (value "1uF 6.3v")
      (footprint "eagle-import:0805")
      (libsource (lib "eagle-import") (part "1.0UF-0805-25V-(+80/-20%)"))
    )
    (comp (ref "C8")
      (value "10uF 6.3V X5R")
      (footprint "eagle-import:0805")
      (libsource (lib "eagle-import") (part "1.0UF-0805-25V-(+80/-20%)"))
    )
    (comp (ref "D3")
      (value "WL-SMCW-150120BS75000-B")
      (footprint "eagle-import:WL-SMCW_1206")
      (libsource (lib "eagle-import") (part "WL-SMCW-150120BS75000-B"))
    )
    (comp (ref "J1")
      (value "CONN_02")
      (footprint "eagle-import:1X02")
      (libsource (lib "eagle-import") (part "CONN_02"))
    )
    (comp (ref "J4")
      (value "CONN_02")
      (footprint "eagle-import:1X02")
      (libsource (lib "eagle-import") (part "CONN_02"))
    )
    (comp (ref "R1")
      (value "4.7k 1%")
      (footprint "eagle-import:0805")
      (libsource (lib "eagle-import") (part "0.3OHM-0805-1/8W-1%"))
    )
    (comp (ref "R2")
      (value "4.7k")
      (footprint "eagle-import:0805")
      (libsource (lib "eagle-import") (part "0.3OHM-0805-1/8W-1%"))
    )
    (comp (ref "R4")
      (value "330")
      (footprint "eagle-import:0805")
      (libsource (lib "eagle-import") (part "0.3OHM-0805-1/8W-1%"))
    )
    (comp (ref "U16")
      (value "BM71BLES1FC2")
      (footprint "eagle-import:RN4871")
      (libsource (lib "eagle-import") (part "BM71BLES1FC2"))
    )
    (comp (ref "J2")
      (value "CONN_11")
      (footprint "eagle-import:1X11")
      (libsource (lib "eagle-import") (part "CONN_11"))
    )
  )
  (nets
    (net (code "1") (name "3.3V") (class "Default")
      (node (ref "C21") (pin "1") (pinfunction "1_1") (pintype "passive"))
      (node (ref "C8") (pin "1") (pinfunction "1_1") (pintype "passive"))
      (node (ref "D3") (pin "2") (pinfunction "+_2") (pintype "passive"))
      (node (ref "J4") (pin "1") (pinfunction "1_1") (pintype "passive"))
      (node (ref "J4") (pin "2") (pinfunction "2_2") (pintype "passive"))
      (node (ref "J5") (pin "13") (pinfunction "13_13") (pintype "passive"))
      (node (ref "J6") (pin "6") (pinfunction "6_6") (pintype "passive"))
      (node (ref "R12") (pin "2") (pinfunction "2_2") (pintype "passive"))
      (node (ref "R16") (pin "2") (pinfunction "2_2") (pintype "passive"))
      (node (ref "R2") (pin "2") (pinfunction "2_2") (pintype "passive"))
      (node (ref "R24") (pin "2") (pinfunction "2_2") (pintype "passive"))
      (node (ref "R27") (pin "2") (pinfunction "2_2") (pintype "passive"))
      (node (ref "R28") (pin "2") (pinfunction "2_2") (pintype "passive"))
      (node (ref "R32") (pin "2") (pinfunction "2_2") (pintype "passive"))
      (node (ref "R43") (pin "2") (pinfunction "2_2") (pintype "passive"))
      (node (ref "R45") (pin "2") (pinfunction "2_2") (pintype "passive"))
      (node (ref "R46") (pin "2") (pinfunction "2_2") (pintype "passive"))
      (node (ref "R8") (pin "2") (pinfunction "2_2") (pintype "passive"))
      (node (ref "R9") (pin "2") (pinfunction "2_2") (pintype "passive"))
      (node (ref "U1") (pin "11") (pinfunction "VIO_11") (pintype "power_in"))
      (node (ref "U16") (pin "14") (pinfunction "VBAT_14") (pintype "power_in"))
      (node (ref "U19") (pin "2") (pinfunction "OUT_2") (pintype "passive"))
      (node (ref "U19") (pin "4") (pinfunction "OUT_4") (pintype "passive"))
    )
    (net (code "2") (name "5V") (class "Default")
      (node (ref "C17") (pin "1") (pinfunction "1_1") (pintype "passive"))
      (node (ref "C5") (pin "1") (pinfunction "1_1") (pintype "passive"))
      (node (ref "D26") (pin "A") (pinfunction "A_A") (pintype "passive"))
      (node (ref "R15") (pin "2") (pinfunction "2_2") (pintype "passive"))
      (node (ref "R26") (pin "2") (pinfunction "2_2") (pintype "passive"))
      (node (ref "U1") (pin "3") (pinfunction "VCC_3") (pintype "power_in"))
      (node (ref "U15") (pin "2") (pinfunction "OUT_2") (pintype "passive"))
    )
    (net (code "3") (name "DLC") (class "Default")
      (node (ref "C10") (pin "1") (pinfunction "1_1") (pintype "passive"))
      (node (ref "C12") (pin "2") (pinfunction "+_2") (pintype "passive"))
      (node (ref "C13") (pin "1") (pinfunction "1_1") (pintype "passive"))
      (node (ref "C18") (pin "1") (pinfunction "1_1") (pintype "passive"))
      (node (ref "C19") (pin "1") (pinfunction "1_1") (pintype "passive"))
      (node (ref "C9") (pin "1") (pinfunction "1_1") (pintype "passive"))
      (node (ref "D30") (pin "C") (pinfunction "C_C") (pintype "passive"))
      (node (ref "IC2") (pin "3") (pinfunction "V+_3") (pintype "power_in"))
      (node (ref "R14") (pin "2") (pinfunction "2_2") (pintype "passive"))
      (node (ref "R33") (pin "2") (pinfunction "2_2") (pintype "passive"))
      (node (ref "R34") (pin "2") (pinfunction "2_2") (pintype "passive"))
      (node (ref "R39") (pin "2") (pinfunction "2_2") (pintype "passive"))
      (node (ref "U10") (pin "5") (pinfunction "VBAT_5") (pintype "power_in"))
      (node (ref "U15") (pin "3") (pinfunction "IN_3") (pintype "input"))
      (node (ref "U19") (pin "3") (pinfunction "IN_3") (pintype "input"))
      (node (ref "U9") (pin "3") (pinfunction "IN_3") (pintype "input"))
    )
    (net (code "4") (name "DLC_RAW") (class "Default")
      (node (ref "C16") (pin "1") (pinfunction "1_1") (pintype "passive"))
      (node (ref "F5") (pin "1") (pinfunction "1_1") (pintype "bidirectional"))
      (node (ref "J2") (pin "11") (pinfunction "11_11") (pintype "passive"))
      (node (ref "J6") (pin "14") (pinfunction "14_14") (pintype "passive"))
    )
    (net (code "5") (name "GND") (class "Default")
      (node (ref "C1") (pin "2") (pinfunction "2_2") (pintype "passive"))
      (node (ref "C10") (pin "2") (pinfunction "2_2") (pintype "passive"))
      (node (ref "C11") (pin "2") (pinfunction "2_2") (pintype "passive"))
      (node (ref "C12") (pin "1") (pinfunction "-_1") (pintype "passive"))
      (node (ref "C13") (pin "2") (pinfunction "2_2") (pintype "passive"))
      (node (ref "C16") (pin "2") (pinfunction "2_2") (pintype "passive"))
      (node (ref "C17") (pin "2") (pinfunction "2_2") (pintype "passive"))
      (node (ref "C18") (pin "2") (pinfunction "2_2") (pintype "passive"))
      (node (ref "C19") (pin "2") (pinfunction "2_2") (pintype "passive"))
      (node (ref "C2") (pin "2") (pinfunction "2_2") (pintype "passive"))
      (node (ref "C20") (pin "2") (pinfunction "2_2") (pintype "passive"))
      (node (ref "C21") (pin "2") (pinfunction "2_2") (pintype "passive"))
      (node (ref "C22") (pin "2") (pinfunction "2_2") (pintype "passive"))
      (node (ref "C23") (pin "2") (pinfunction "2_2") (pintype "passive"))
      (node (ref "C3") (pin "2") (pinfunction "2_2") (pintype "passive"))
      (node (ref "C4") (pin "2") (pinfunction "2_2") (pintype "passive"))
      (node (ref "C5") (pin "2") (pinfunction "2_2") (pintype "passive"))
      (node (ref "C6") (pin "2") (pinfunction "2_2") (pintype "passive"))
      (node (ref "C7") (pin "2") (pinfunction "2_2") (pintype "passive"))
      (node (ref "C8") (pin "2") (pinfunction "2_2") (pintype "passive"))
      (node (ref "C9") (pin "2") (pinfunction "2_2") (pintype "passive"))
      (node (ref "CP1202N") (pin "12") (pinfunction "GND_12") (pintype "power_in"))
      (node (ref "CP1202N") (pin "3") (pinfunction "GND_3") (pintype "power_in"))
      (node (ref "D1") (pin "2") (pinfunction "A2_2") (pintype "passive"))
      (node (ref "D18") (pin "3") (pinfunction "3_3") (pintype "bidirectional"))
      (node (ref "D19") (pin "3") (pinfunction "3_3") (pintype "bidirectional"))
      (node (ref "D2") (pin "1") (pinfunction "1_1") (pintype "passive"))
      (node (ref "D22") (pin "A") (pinfunction "A_A") (pintype "passive"))
      (node (ref "D24") (pin "A") (pinfunction "A_A") (pintype "passive"))
      (node (ref "D25") (pin "A") (pinfunction "A_A") (pintype "passive"))
      (node (ref "D31") (pin "C") (pinfunction "C_C") (pintype "passive"))
      (node (ref "D32") (pin "A") (pinfunction "1_A") (pintype "passive"))
      (node (ref "D4") (pin "1") (pinfunction "-_1") (pintype "passive"))
      (node (ref "D5") (pin "1") (pinfunction "-_1") (pintype "passive"))
      (node (ref "D6") (pin "1") (pinfunction "-_1") (pintype "passive"))
      (node (ref "D7") (pin "A") (pinfunction "A_A") (pintype "passive"))
      (node (ref "IC2") (pin "10") (pinfunction "-IN_10") (pintype "input"))
      (node (ref "IC2") (pin "11") (pinfunction "+IN_11") (pintype "input"))
      (node (ref "IC2") (pin "12") (pinfunction "GND_12") (pintype "power_in"))
      (node (ref "IC2") (pin "13") (pinfunction "OUT_13") (pintype "open_collector"))
      (node (ref "J1") (pin "1") (pinfunction "1_1") (pintype "passive"))
      (node (ref "J2") (pin "6") (pinfunction "6_6") (pintype "passive"))
      (node (ref "J3") (pin "GND") (pinfunction "GND_GND") (pintype "power_in"))
      (node (ref "J3") (pin "SHLD1") (pinfunction "SHIELD_SHLD1") (pintype "bidirectional"))
      (node (ref "J3") (pin "SHLD2") (pinfunction "SHIELD_SHLD2") (pintype "bidirectional"))
      (node (ref "J5") (pin "14") (pinfunction "14_14") (pintype "passive"))
      (node (ref "J6") (pin "1") (pinfunction "1_1") (pintype "passive"))
      (node (ref "J6") (pin "13") (pinfunction "13_13") (pintype "passive"))
      (node (ref "R21") (pin "2") (pinfunction "2_2") (pintype "passive"))
      (node (ref "R25") (pin "1") (pinfunction "1_1") (pintype "passive"))
      (node (ref "R31") (pin "1") (pinfunction "1_1") (pintype "passive"))
      (node (ref "R37") (pin "1") (pinfunction "1_1") (pintype "passive"))
      (node (ref "R38") (pin "1") (pinfunction "1_1") (pintype "passive"))
      (node (ref "R41") (pin "1") (pinfunction "1_1") (pintype "passive"))
      (node (ref "T1") (pin "2") (pinfunction "S_2") (pintype "passive"))
      (node (ref "T2") (pin "2") (pinfunction "S_2") (pintype "passive"))
      (node (ref "T3") (pin "2") (pinfunction "S_2") (pintype "passive"))
      (node (ref "T6") (pin "2") (pinfunction "S_2") (pintype "passive"))
      (node (ref "T7") (pin "E") (pinfunction "E_E") (pintype "passive"))
      (node (ref "T8") (pin "E") (pinfunction "E_E") (pintype "passive"))
      (node (ref "U1") (pin "2") (pinfunction "GNDA_2") (pintype "power_in"))
      (node (ref "U1") (pin "5") (pinfunction "GNDB_5") (pintype "power_in"))
      (node (ref "U10") (pin "8") (pinfunction "GND_8") (pintype "power_in"))
      (node (ref "U15") (pin "1") (pinfunction "GND_1") (pintype "input"))
      (node (ref "U16") (pin "13") (pinfunction "GND_13") (pintype "power_in"))
      (node (ref "U16") (pin "2") (pinfunction "GND_2") (pintype "power_in"))
      (node (ref "U19") (pin "1") (pinfunction "GND_1") (pintype "input"))
    )
    (net (code "6") (name "HS_CAN_H") (class "Default")
      (node (ref "D18") (pin "2") (pinfunction "2_2") (pintype "bidirectional"))
      (node (ref "J2") (pin "4") (pinfunction "4_4") (pintype "passive"))
      (node (ref "R20") (pin "2") (pinfunction "2_2") (pintype "passive"))
      (node (ref "U1") (pin "10") (pinfunction "CANH2_10") (pintype "input"))
    )
    (net (code "7") (name "HS_CAN_L") (class "Default")
      (node (ref "D18") (pin "1") (pinfunction "1_1") (pintype "bidirectional"))
      (node (ref "J2") (pin "5") (pinfunction "5_5") (pintype "passive"))
      (node (ref "R19") (pin "2") (pinfunction "2_2") (pintype "passive"))
      (node (ref "U1") (pin "9") (pinfunction "CANL2_9") (pintype "input"))
    )
    (net (code "8") (name "HS_CAN_RX") (class "Default")
      (node (ref "J5") (pin "4") (pinfunction "4_4") (pintype "passive"))
      (node (ref "U1") (pin "7") (pinfunction "RXD2_7") (pintype "input"))
    )
    (net (code "9") (name "HS_CAN_TX") (class "Default")
      (node (ref "J5") (pin "5") (pinfunction "5_5") (pintype "passive"))
      (node (ref "R45") (pin "1") (pinfunction "1_1") (pintype "passive"))
      (node (ref "U1") (pin "6") (pinfunction "TXD2_6") (pintype "output"))
    )
    (net (code "10") (name "J1850_BUS+") (class "Default")
      (node (ref "D25") (pin "C") (pinfunction "C_C") (pintype "passive"))
      (node (ref "D28") (pin "C") (pinfunction "C_C") (pintype "passive"))
      (node (ref "IC2") (pin "7") (pinfunction "+IN_7") (pintype "input"))
      (node (ref "J2") (pin "9") (pinfunction "9_9") (pintype "passive"))
      (node (ref "R22") (pin "2") (pinfunction "2_2") (pintype "passive"))
      (node (ref "R23") (pin "1") (pinfunction "1_1") (pintype "passive"))
      (node (ref "R23") (pin "2") (pinfunction "2_2") (pintype "passive"))
      (node (ref "R29") (pin "1") (pinfunction "1_1") (pintype "passive"))
    )
    (net (code "11") (name "J1850_BUS+_TX") (class "Default")
      (node (ref "J6") (pin "10") (pinfunction "10_10") (pintype "passive"))
      (node (ref "R37") (pin "2") (pinfunction "2_2") (pintype "passive"))
      (node (ref "T6") (pin "1") (pinfunction "G_1") (pintype "passive"))
    )
    (net (code "12") (name "J1850_BUS-") (class "Default")
      (node (ref "D24") (pin "C") (pinfunction "C_C") (pintype "passive"))
      (node (ref "IC2") (pin "6") (pinfunction "-IN_6") (pintype "input"))
      (node (ref "J2") (pin "10") (pinfunction "10_10") (pintype "passive"))
      (node (ref "R36") (pin "1") (pinfunction "1_1") (pintype "passive"))
      (node (ref "R7") (pin "1") (pinfunction "1_1") (pintype "passive"))
      (node (ref "R7") (pin "2") (pinfunction "2_2") (pintype "passive"))
      (node (ref "T2") (pin "3") (pinfunction "D_3") (pintype "passive"))
    )
    (net (code "13") (name "K_LINE") (class "Default")
      (node (ref "J2") (pin "7") (pinfunction "7_7") (pintype "passive"))
      (node (ref "R34") (pin "1") (pinfunction "1_1") (pintype "passive"))
      (node (ref "R42") (pin "1") (pinfunction "1_1") (pintype "passive"))
      (node (ref "T7") (pin "C") (pinfunction "C_C") (pintype "passive"))
    )
    (net (code "14") (name "L_LINE") (class "Default")
      (node (ref "J2") (pin "8") (pinfunction "8_8") (pintype "passive"))
      (node (ref "R33") (pin "1") (pinfunction "1_1") (pintype "passive"))
      (node (ref "T8") (pin "C") (pinfunction "C_C") (pintype "passive"))
    )
    (net (code "15") (name "MS_CAN_H") (class "Default")
      (node (ref "D19") (pin "2") (pinfunction "2_2") (pintype "bidirectional"))
      (node (ref "J2") (pin "2") (pinfunction "2_2") (pintype "passive"))
      (node (ref "R18") (pin "2") (pinfunction "2_2") (pintype "passive"))
      (node (ref "U1") (pin "13") (pinfunction "CANH1_13") (pintype "input"))
    )
    (net (code "16") (name "MS_CAN_L") (class "Default")
      (node (ref "D19") (pin "1") (pinfunction "1_1") (pintype "bidirectional"))
      (node (ref "J2") (pin "3") (pinfunction "3_3") (pintype "passive"))
      (node (ref "R17") (pin "2") (pinfunction "2_2") (pintype "passive"))
      (node (ref "U1") (pin "12") (pinfunction "CANL1_12") (pintype "input"))
    )
    (net (code "17") (name "MS_CAN_RX") (class "Default")
      (node (ref "J5") (pin "6") (pinfunction "6_6") (pintype "passive"))
      (node (ref "U1") (pin "4") (pinfunction "RXD1_4") (pintype "input"))
    )
    (net (code "18") (name "MS_CAN_TX") (class "Default")
      (node (ref "J5") (pin "7") (pinfunction "7_7") (pintype "passive"))
      (node (ref "R24") (pin "1") (pinfunction "1_1") (pintype "passive"))
      (node (ref "U1") (pin "1") (pinfunction "TXD1_1") (pintype "output"))
    )
    (net (code "19") (name "Net-(C11-Pad1)") (class "Default")
      (node (ref "C11") (pin "1") (pinfunction "1_1") (pintype "passive"))
      (node (ref "R17") (pin "1") (pinfunction "1_1") (pintype "passive"))
    )
    (net (code "20") (name "Net-(C20-Pad1)") (class "Default")
      (node (ref "C20") (pin "1") (pinfunction "1_1") (pintype "passive"))
      (node (ref "R18") (pin "1") (pinfunction "1_1") (pintype "passive"))
    )
    (net (code "21") (name "Net-(C22-Pad1)") (class "Default")
      (node (ref "C22") (pin "1") (pinfunction "1_1") (pintype "passive"))
      (node (ref "R19") (pin "1") (pinfunction "1_1") (pintype "passive"))
    )
    (net (code "22") (name "Net-(C23-Pad1)") (class "Default")
      (node (ref "C23") (pin "1") (pinfunction "1_1") (pintype "passive"))
      (node (ref "R20") (pin "1") (pinfunction "1_1") (pintype "passive"))
    )
    (net (code "23") (name "Net-(CP1202N-D+)") (class "Default")
      (node (ref "CP1202N") (pin "4") (pinfunction "D+_4") (pintype "input"))
      (node (ref "D2") (pin "4") (pinfunction "4_4") (pintype "passive"))
      (node (ref "J3") (pin "D+") (pinfunction "D+_D+") (pintype "bidirectional"))
    )
    (net (code "24") (name "Net-(CP1202N-D-)") (class "Default")
      (node (ref "CP1202N") (pin "5") (pinfunction "D-_5") (pintype "input"))
      (node (ref "D2") (pin "3") (pinfunction "3_3") (pintype "passive"))
      (node (ref "J3") (pin "D-") (pinfunction "D-_D-") (pintype "bidirectional"))
    )
    (net (code "25") (name "Net-(CP1202N-GPIO2{slash}TXT)") (class "Default")
      (node (ref "CP1202N") (pin "20") (pinfunction "GPIO2/TXT_20") (pintype "bidirectional"))
      (node (ref "D8") (pin "1") (pinfunction "-_1") (pintype "passive"))
    )
    (net (code "26") (name "Net-(CP1202N-GPIO3{slash}RXT)") (class "Default")
      (node (ref "CP1202N") (pin "19") (pinfunction "GPIO3/RXT_19") (pintype "bidirectional"))
      (node (ref "D9") (pin "1") (pinfunction "-_1") (pintype "passive"))
    )
    (net (code "27") (name "Net-(CP1202N-RSTB)") (class "Default")
      (node (ref "CP1202N") (pin "9") (pinfunction "RSTB_9") (pintype "input"))
      (node (ref "R3") (pin "2") (pinfunction "2_2") (pintype "passive"))
    )
    (net (code "28") (name "Net-(CP1202N-VBUS)") (class "Default")
      (node (ref "C1") (pin "1") (pinfunction "1_1") (pintype "passive"))
      (node (ref "C2") (pin "1") (pinfunction "1_1") (pintype "passive"))
      (node (ref "CP1202N") (pin "7") (pinfunction "VREGIN_7") (pintype "power_in"))
      (node (ref "CP1202N") (pin "8") (pinfunction "VBUS_8") (pintype "input"))
      (node (ref "D2") (pin "2") (pinfunction "2_2") (pintype "passive"))
      (node (ref "J3") (pin "VBUS") (pinfunction "VBUS_VBUS") (pintype "power_in"))
    )
    (net (code "29") (name "Net-(D3--)") (class "Default")
      (node (ref "D3") (pin "1") (pinfunction "-_1") (pintype "passive"))
      (node (ref "R4") (pin "2") (pinfunction "2_2") (pintype "passive"))
    )
    (net (code "30") (name "Net-(D4-+)") (class "Default")
      (node (ref "D4") (pin "2") (pinfunction "+_2") (pintype "passive"))
      (node (ref "R14") (pin "1") (pinfunction "1_1") (pintype "passive"))
    )
    (net (code "31") (name "Net-(D5-+)") (class "Default")
      (node (ref "D5") (pin "2") (pinfunction "+_2") (pintype "passive"))
      (node (ref "R15") (pin "1") (pinfunction "1_1") (pintype "passive"))
    )
    (net (code "32") (name "Net-(D6-+)") (class "Default")
      (node (ref "D6") (pin "2") (pinfunction "+_2") (pintype "passive"))
      (node (ref "R16") (pin "1") (pinfunction "1_1") (pintype "passive"))
    )
    (net (code "33") (name "Net-(D8-+)") (class "Default")
      (node (ref "D8") (pin "2") (pinfunction "+_2") (pintype "passive"))
      (node (ref "R5") (pin "1") (pinfunction "1_1") (pintype "passive"))
    )
    (net (code "34") (name "Net-(D9-+)") (class "Default")
      (node (ref "D9") (pin "2") (pinfunction "+_2") (pintype "passive"))
      (node (ref "R6") (pin "1") (pinfunction "1_1") (pintype "passive"))
    )
    (net (code "35") (name "Net-(D26-PadC)") (class "Default")
      (node (ref "D26") (pin "C") (pinfunction "C_C") (pintype "passive"))
      (node (ref "R36") (pin "2") (pinfunction "2_2") (pintype "passive"))
    )
    (net (code "36") (name "Net-(D31-PadA)") (class "Default")
      (node (ref "D31") (pin "A") (pinfunction "A_A") (pintype "passive"))
      (node (ref "R22") (pin "1") (pinfunction "1_1") (pintype "passive"))
    )
    (net (code "37") (name "Net-(D32-2)") (class "Default")
      (node (ref "D30") (pin "A") (pinfunction "A_A") (pintype "passive"))
      (node (ref "D32") (pin "C") (pinfunction "2_C") (pintype "passive"))
      (node (ref "F5") (pin "2") (pinfunction "2_2") (pintype "bidirectional"))
    )
    (net (code "38") (name "Net-(IC2A-+IN)") (class "Default")
      (node (ref "D22") (pin "C") (pinfunction "C_C") (pintype "passive"))
      (node (ref "IC2") (pin "5") (pinfunction "+IN_5") (pintype "input"))
      (node (ref "R29") (pin "2") (pinfunction "2_2") (pintype "passive"))
    )
    (net (code "39") (name "Net-(IC2A--IN)") (class "Default")
      (node (ref "IC2") (pin "4") (pinfunction "-IN_4") (pintype "input"))
      (node (ref "R25") (pin "2") (pinfunction "2_2") (pintype "passive"))
      (node (ref "R26") (pin "1") (pinfunction "1_1") (pintype "passive"))
    )
    (net (code "40") (name "Net-(IC2C-+IN)") (class "Default")
      (node (ref "IC2") (pin "9") (pinfunction "+IN_9") (pintype "input"))
      (node (ref "R39") (pin "1") (pinfunction "1_1") (pintype "passive"))
      (node (ref "R41") (pin "2") (pinfunction "2_2") (pintype "passive"))
    )
    (net (code "41") (name "Net-(IC2C--IN)") (class "Default")
      (node (ref "D7") (pin "C") (pinfunction "C_C") (pintype "passive"))
      (node (ref "IC2") (pin "8") (pinfunction "-IN_8") (pintype "input"))
      (node (ref "R42") (pin "2") (pinfunction "2_2") (pintype "passive"))
    )
    (net (code "42") (name "Net-(J1-Pad2)") (class "Default")
      (node (ref "J1") (pin "2") (pinfunction "2_2") (pintype "passive"))
      (node (ref "R1") (pin "1") (pinfunction "1_1") (pintype "passive"))
    )
    (net (code "43") (name "Net-(R11-Pad2)") (class "Default")
      (node (ref "R11") (pin "2") (pinfunction "2_2") (pintype "passive"))
      (node (ref "T7") (pin "B") (pinfunction "B_B") (pintype "passive"))
    )
    (net (code "44") (name "Net-(R35-Pad2)") (class "Default")
      (node (ref "R35") (pin "2") (pinfunction "2_2") (pintype "passive"))
      (node (ref "T8") (pin "B") (pinfunction "B_B") (pintype "passive"))
    )
    (net (code "45") (name "Net-(T1-D)") (class "Default")
      (node (ref "R13") (pin "1") (pinfunction "1_1") (pintype "passive"))
      (node (ref "T1") (pin "3") (pinfunction "D_3") (pintype "passive"))
    )
    (net (code "46") (name "Net-(T3-D)") (class "Default")
      (node (ref "R30") (pin "1") (pinfunction "1_1") (pintype "passive"))
      (node (ref "R31") (pin "2") (pinfunction "2_2") (pintype "passive"))
      (node (ref "T3") (pin "3") (pinfunction "D_3") (pintype "passive"))
    )
    (net (code "47") (name "Net-(T6-D)") (class "Default")
      (node (ref "R44") (pin "1") (pinfunction "1_1") (pintype "passive"))
      (node (ref "T6") (pin "3") (pinfunction "D_3") (pintype "passive"))
      (node (ref "T9") (pin "1") (pinfunction "G_1") (pintype "passive"))
    )
    (net (code "48") (name "Net-(T9-D)") (class "Default")
      (node (ref "D28") (pin "A") (pinfunction "A_A") (pintype "passive"))
      (node (ref "T9") (pin "3") (pinfunction "D_3") (pintype "passive"))
    )
    (net (code "49") (name "Net-(U1-STBN1)") (class "Default")
      (node (ref "R8") (pin "1") (pinfunction "1_1") (pintype "passive"))
      (node (ref "U1") (pin "14") (pinfunction "STBN1_14") (pintype "input"))
    )
    (net (code "50") (name "Net-(U1-STBN2)") (class "Default")
      (node (ref "R9") (pin "1") (pinfunction "1_1") (pintype "passive"))
      (node (ref "U1") (pin "8") (pinfunction "STBN2_8") (pintype "input"))
    )
    (net (code "51") (name "Net-(U9-ADJ)") (class "Default")
      (node (ref "R10") (pin "1") (pinfunction "1_1") (pintype "passive"))
      (node (ref "R30") (pin "2") (pinfunction "2_2") (pintype "passive"))
      (node (ref "U9") (pin "1") (pinfunction "ADJ_1") (pintype "input"))
    )
    (net (code "52") (name "Net-(U10-LOAD)") (class "Default")
      (node (ref "R40") (pin "1") (pinfunction "1_1") (pintype "passive"))
      (node (ref "U10") (pin "6") (pinfunction "LOAD_6") (pintype "output"))
    )
    (net (code "53") (name "Net-(U16-P0_2)") (class "Default")
      (node (ref "R4") (pin "1") (pinfunction "1_1") (pintype "passive"))
      (node (ref "U16") (pin "12") (pinfunction "P0_2_12") (pintype "bidirectional"))
    )
    (net (code "54") (name "Net-(U16-P2_0)") (class "Default")
      (node (ref "R1") (pin "2") (pinfunction "2_2") (pintype "passive"))
      (node (ref "U16") (pin "16") (pinfunction "P2_0_16") (pintype "input"))
    )
    (net (code "55") (name "Net-(U16-RST_N)") (class "Default")
      (node (ref "C7") (pin "1") (pinfunction "1_1") (pintype "passive"))
      (node (ref "R2") (pin "1") (pinfunction "1_1") (pintype "passive"))
      (node (ref "U16") (pin "10") (pinfunction "RST_N_10") (pintype "input"))
    )
    (net (code "56") (name "PWM_RX") (class "Default")
      (node (ref "IC2") (pin "1") (pinfunction "OUT_1") (pintype "open_collector"))
      (node (ref "J6") (pin "9") (pinfunction "9_9") (pintype "passive"))
      (node (ref "R28") (pin "1") (pinfunction "1_1") (pintype "passive"))
    )
    (net (code "57") (name "PWM{slash}~{VPW}") (class "Default")
      (node (ref "J6") (pin "7") (pinfunction "7_7") (pintype "passive"))
      (node (ref "R32") (pin "1") (pinfunction "1_1") (pintype "passive"))
      (node (ref "T3") (pin "1") (pinfunction "G_1") (pintype "passive"))
    )
    (net (code "58") (name "SW_CAN") (class "Default")
      (node (ref "C6") (pin "1") (pinfunction "1_1") (pintype "passive"))
      (node (ref "D1") (pin "1") (pinfunction "A1_1") (pintype "passive"))
      (node (ref "J2") (pin "1") (pinfunction "1_1") (pintype "passive"))
      (node (ref "R13") (pin "2") (pinfunction "2_2") (pintype "passive"))
      (node (ref "R40") (pin "2") (pinfunction "2_2") (pintype "passive"))
      (node (ref "U10") (pin "7") (pinfunction "CANH_7") (pintype "bidirectional"))
    )
    (net (code "59") (name "SW_CAN_LOAD") (class "Default")
      (node (ref "J5") (pin "12") (pinfunction "12_12") (pintype "passive"))
      (node (ref "R21") (pin "1") (pinfunction "1_1") (pintype "passive"))
      (node (ref "T1") (pin "1") (pinfunction "G_1") (pintype "passive"))
    )
    (net (code "60") (name "SW_CAN_MODE0") (class "Default")
      (node (ref "J5") (pin "10") (pinfunction "10_10") (pintype "passive"))
      (node (ref "U10") (pin "2") (pinfunction "MODE0_2") (pintype "input"))
    )
    (net (code "61") (name "SW_CAN_MODE1") (class "Default")
      (node (ref "J5") (pin "11") (pinfunction "11_11") (pintype "passive"))
      (node (ref "U10") (pin "3") (pinfunction "MODE1_3") (pintype "input"))
    )
    (net (code "62") (name "SW_CAN_RX") (class "Default")
      (node (ref "J5") (pin "8") (pinfunction "8_8") (pintype "passive"))
      (node (ref "R12") (pin "1") (pinfunction "1_1") (pintype "passive"))
      (node (ref "U10") (pin "4") (pinfunction "RX_4") (pintype "input"))
    )
    (net (code "63") (name "SW_CAN_TX") (class "Default")
      (node (ref "J5") (pin "9") (pinfunction "9_9") (pintype "passive"))
      (node (ref "R46") (pin "1") (pinfunction "1_1") (pintype "passive"))
      (node (ref "U10") (pin "1") (pinfunction "TX_1") (pintype "input"))
    )
    (net (code "64") (name "UART_RX") (class "Default")
      (node (ref "CP1202N") (pin "18") (pinfunction "TXD_18") (pintype "output"))
      (node (ref "J5") (pin "1") (pinfunction "1_1") (pintype "passive"))
      (node (ref "U16") (pin "8") (pinfunction "HCI_TXD_8") (pintype "output"))
    )
    (net (code "65") (name "UART_TX") (class "Default")
      (node (ref "CP1202N") (pin "17") (pinfunction "RXD_17") (pintype "input"))
      (node (ref "J5") (pin "2") (pinfunction "2_2") (pintype "passive"))
      (node (ref "U16") (pin "7") (pinfunction "HCI_RXD_7") (pintype "input"))
    )
    (net (code "66") (name "VDD_CP") (class "Default")
      (node (ref "C3") (pin "1") (pinfunction "1_1") (pintype "passive"))
      (node (ref "C4") (pin "1") (pinfunction "1_1") (pintype "passive"))
      (node (ref "CP1202N") (pin "6") (pinfunction "VDD_6") (pintype "power_in"))
      (node (ref "R3") (pin "1") (pinfunction "1_1") (pintype "passive"))
      (node (ref "R5") (pin "2") (pinfunction "2_2") (pintype "passive"))
      (node (ref "R6") (pin "2") (pinfunction "2_2") (pintype "passive"))
    )
    (net (code "67") (name "VPW_RX") (class "Default")
      (node (ref "IC2") (pin "2") (pinfunction "OUT_2") (pintype "open_collector"))
      (node (ref "J6") (pin "8") (pinfunction "8_8") (pintype "passive"))
      (node (ref "R27") (pin "1") (pinfunction "1_1") (pintype "passive"))
    )
    (net (code "68") (name "V_J1850") (class "Default")
      (node (ref "R10") (pin "2") (pinfunction "2_2") (pintype "passive"))
      (node (ref "R44") (pin "2") (pinfunction "2_2") (pintype "passive"))
      (node (ref "T9") (pin "2") (pinfunction "S_2") (pintype "passive"))
      (node (ref "U9") (pin "2") (pinfunction "OUT_2") (pintype "output"))
      (node (ref "U9") (pin "4") (pinfunction "OUT_4") (pintype "output"))
    )
    (net (code "69") (name "unconnected-(CP1202N-GPIO0{slash}CLK-Pad2)") (class "Default")
      (node (ref "CP1202N") (pin "2") (pinfunction "GPIO0/CLK_2") (pintype "bidirectional"))
    )
    (net (code "70") (name "unconnected-(CP1202N-GPIO1{slash}RS485-Pad1)") (class "Default")
      (node (ref "CP1202N") (pin "1") (pinfunction "GPIO1/RS485_1") (pintype "bidirectional"))
    )
    (net (code "71") (name "unconnected-(CP1202N-NC-Pad10)") (class "Default")
      (node (ref "CP1202N") (pin "10") (pinfunction "NC_10") (pintype "bidirectional"))
    )
    (net (code "72") (name "unconnected-(CP1202N-RTS-Pad16)") (class "Default")
      (node (ref "CP1202N") (pin "16") (pinfunction "RTS_16") (pintype "output"))
    )
    (net (code "73") (name "unconnected-(CP1202N-SUSPEND-Pad14)") (class "Default")
      (node (ref "CP1202N") (pin "14") (pinfunction "SUSPEND_14") (pintype "output"))
    )
    (net (code "74") (name "unconnected-(CP1202N-SUSPENDB-Pad11)") (class "Default")
      (node (ref "CP1202N") (pin "11") (pinfunction "SUSPENDB_11") (pintype "output"))
    )
    (net (code "75") (name "unconnected-(CP1202N-WAKEUP-Pad13)") (class "Default")
      (node (ref "CP1202N") (pin "13") (pinfunction "WAKEUP_13") (pintype "input"))
    )
    (net (code "76") (name "unconnected-(D1-C-Pad3)") (class "Default")
      (node (ref "D1") (pin "3") (pinfunction "C_3") (pintype "passive"))
    )
    (net (code "77") (name "unconnected-(J6-Pad2)") (class "Default")
      (node (ref "J6") (pin "2") (pinfunction "2_2") (pintype "passive"))
    )
    (net (code "78") (name "unconnected-(J6-Pad12)") (class "Default")
      (node (ref "J6") (pin "12") (pinfunction "12_12") (pintype "passive"))
    )
    (net (code "79") (name "unconnected-(U16-BT_RF-Pad1)") (class "Default")
      (node (ref "U16") (pin "1") (pinfunction "BT_RF_1") (pintype "bidirectional"))
    )
    (net (code "80") (name "unconnected-(U16-P0_0-Pad11)") (class "Default")
      (node (ref "U16") (pin "11") (pinfunction "P0_0_11") (pintype "bidirectional"))
    )
    (net (code "81") (name "unconnected-(U16-P1_2-Pad3)") (class "Default")
      (node (ref "U16") (pin "3") (pinfunction "P1_2_3") (pintype "bidirectional"))
    )
    (net (code "82") (name "unconnected-(U16-P1_3-Pad4)") (class "Default")
      (node (ref "U16") (pin "4") (pinfunction "P1_3_4") (pintype "bidirectional"))
    )
    (net (code "83") (name "unconnected-(U16-P1_6-Pad6)") (class "Default")
      (node (ref "U16") (pin "6") (pinfunction "P1_6_6") (pintype "bidirectional"))
    )
    (net (code "84") (name "unconnected-(U16-P1_7-Pad5)") (class "Default")
      (node (ref "U16") (pin "5") (pinfunction "P1_7_5") (pintype "bidirectional"))
    )
    (net (code "85") (name "unconnected-(U16-P2_7-Pad15)") (class "Default")
      (node (ref "U16") (pin "15") (pinfunction "P2_7_15") (pintype "bidirectional"))
    )
    (net (code "86") (name "unconnected-(U16-P3_6-Pad9)") (class "Default")
      (node (ref "U16") (pin "9") (pinfunction "P3_6_9") (pintype "bidirectional"))
    )
    (net (code "87") (name "~{ISO_K_TX}") (class "Default")
      (node (ref "J6") (pin "4") (pinfunction "4_4") (pintype "passive"))
      (node (ref "R11") (pin "1") (pinfunction "1_1") (pintype "passive"))
    )
    (net (code "88") (name "~{ISO_L_TX}") (class "Default")
      (node (ref "J6") (pin "5") (pinfunction "5_5") (pintype "passive"))
      (node (ref "R35") (pin "1") (pinfunction "1_1") (pintype "passive"))
    )
    (net (code "89") (name "~{ISO_RX}") (class "Default")
      (node (ref "IC2") (pin "14") (pinfunction "OUT_14") (pintype "open_collector"))
      (node (ref "J6") (pin "3") (pinfunction "3_3") (pintype "passive"))
      (node (ref "R43") (pin "1") (pinfunction "1_1") (pintype "passive"))
    )
    (net (code "90") (name "~{J1850_BUS-_TX}") (class "Default")
      (node (ref "J6") (pin "11") (pinfunction "11_11") (pintype "passive"))
      (node (ref "R38") (pin "2") (pinfunction "2_2") (pintype "passive"))
      (node (ref "T2") (pin "1") (pinfunction "G_1") (pintype "passive"))
    )
    (net (code "91") (name "~{UART_CTS}") (class "Default")
      (node (ref "CP1202N") (pin "15") (pinfunction "CTS_15") (pintype "input"))
      (node (ref "J5") (pin "3") (pinfunction "3_3") (pintype "passive"))
    )
  )
)
